# CRBN_60.net
KiCad netlist of a schematic drawn in EAGLE
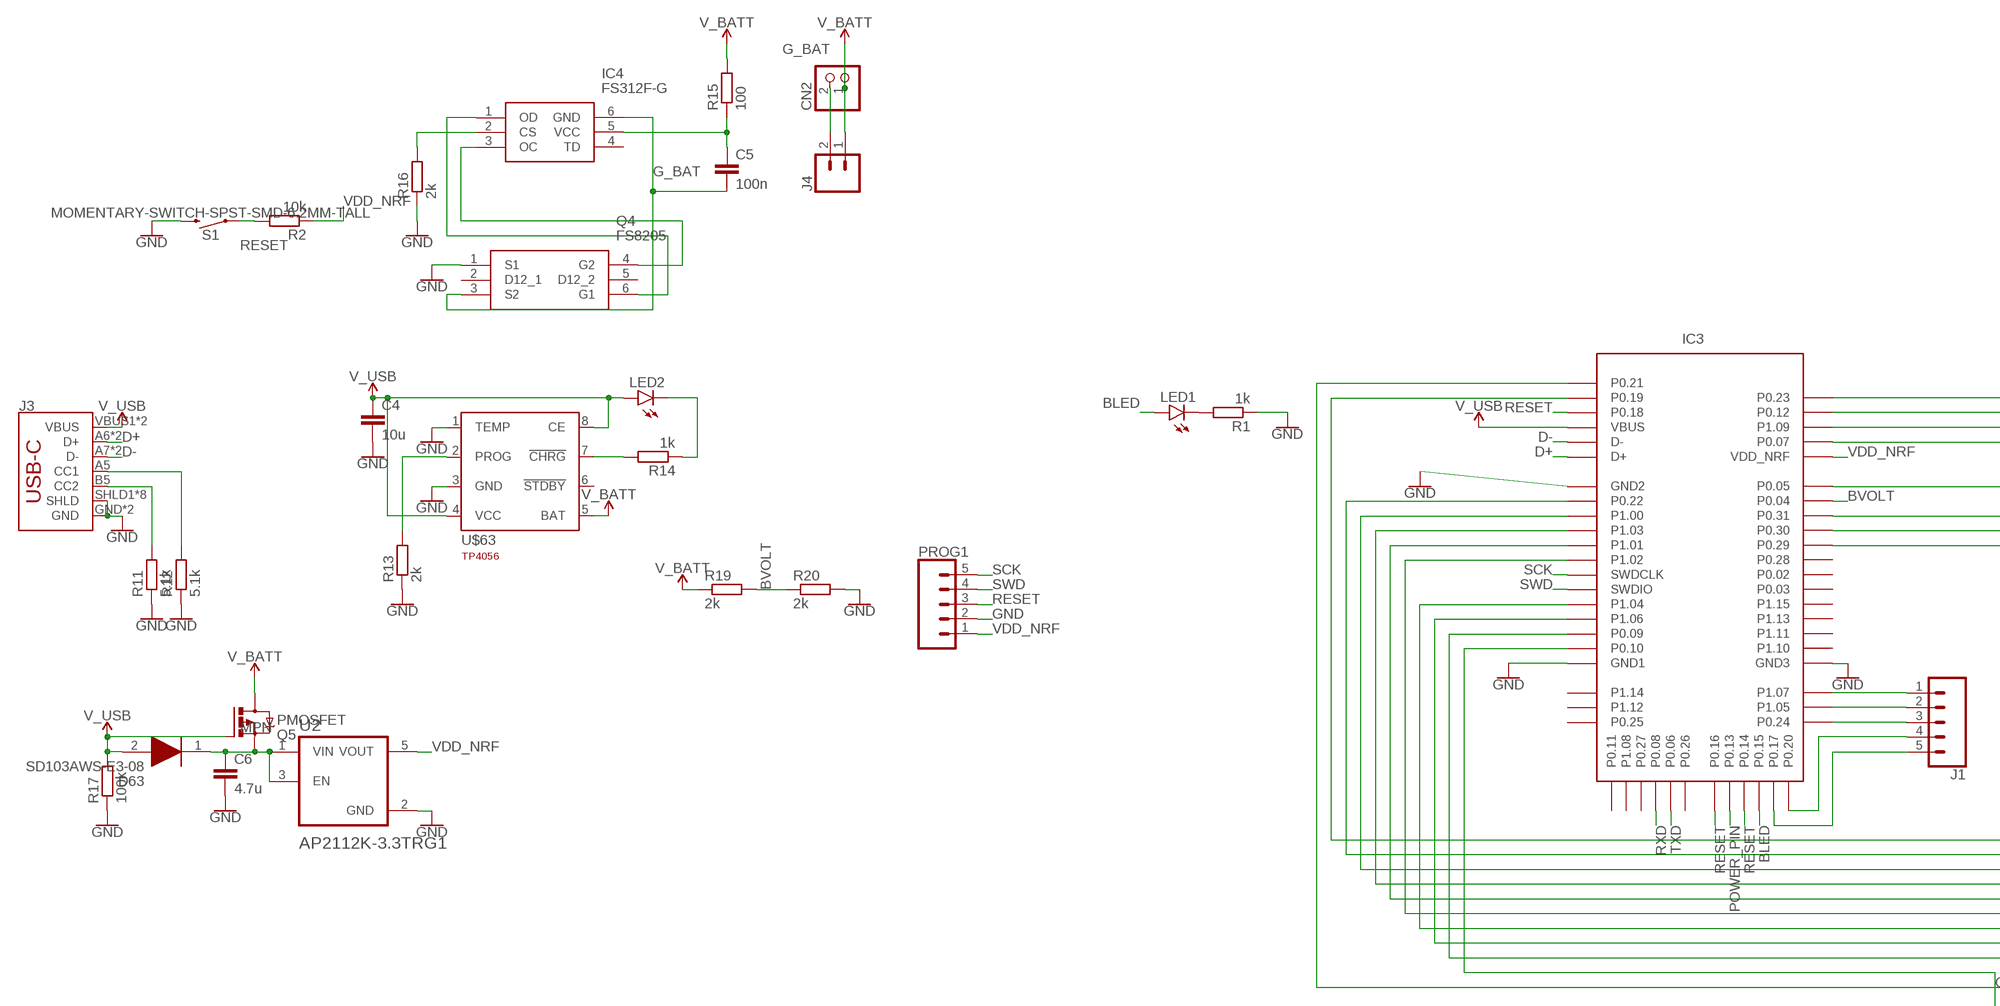
[diagram p0: schematic, sheet 1, part 1 of 2]
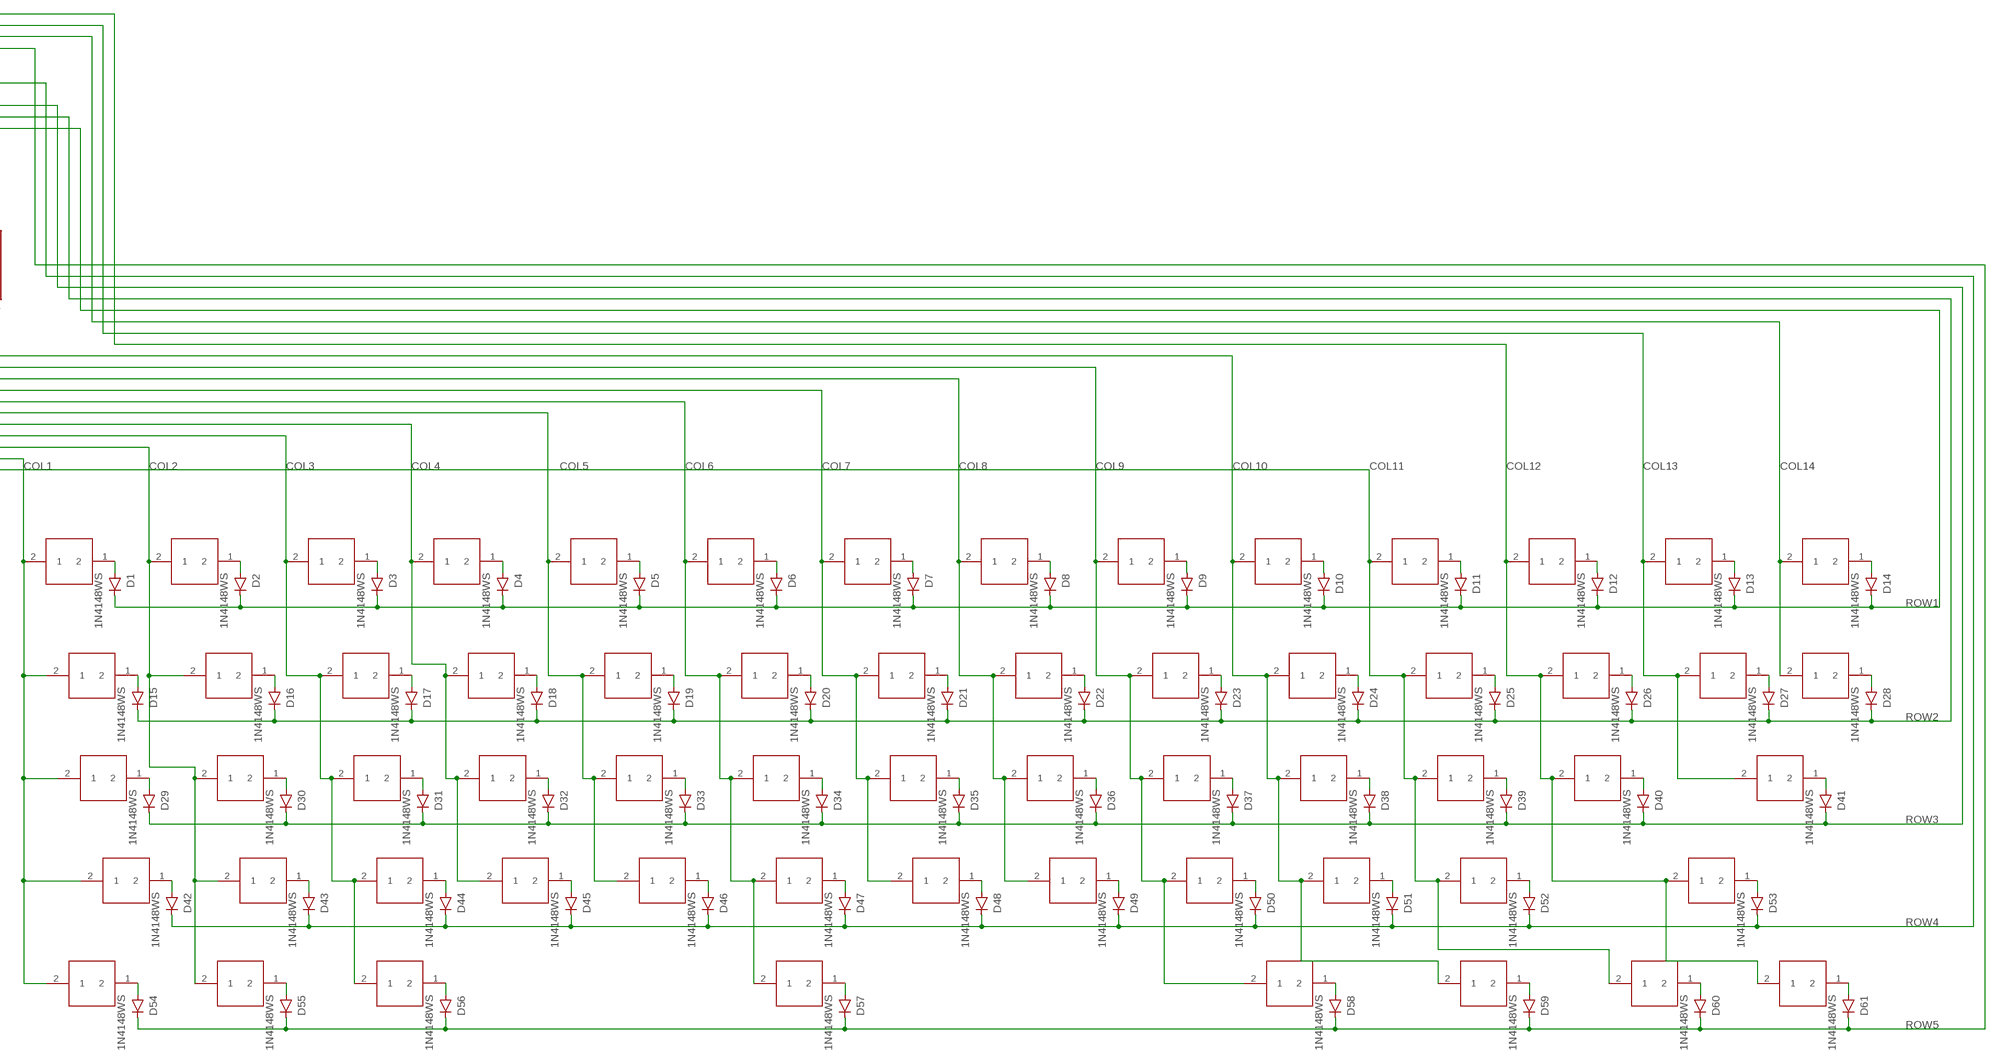
[diagram p1: schematic, sheet 1, part 2 of 2]

(export (version "E")
  (design (tool "Eeschema 10.0.6"))
  (components
    (comp (ref "C4")
      (value "10u")
      (footprint "eagle-import:C0603")
      (libsource (lib "eagle-import") (part "C-EUC0603"))
    )
    (comp (ref "C5")
      (value "100n")
      (footprint "eagle-import:C0603")
      (libsource (lib "eagle-import") (part "C-EUC0603"))
    )
    (comp (ref "C6")
      (value "4.7u")
      (footprint "eagle-import:C0603")
      (libsource (lib "eagle-import") (part "C-EUC0603"))
    )
    (comp (ref "CN2")
      (value "JST_2PIN-SMT")
      (footprint "eagle-import:JST-PH-2-SMT")
      (libsource (lib "eagle-import") (part "JST_2PIN-SMT"))
    )
    (comp (ref "D1")
      (value "1N4148WS")
      (footprint "eagle-import:SOD-323")
      (fields
        (field (name "DIGIKEY_PART_NUMBER") "1N4148WSFSTR-ND")
        (field (name "MANUFACTURER") "Diodes Incorporated")
        (field (name "CREATED_BY") "PCBLayout.com")
      )
      (libsource (lib "eagle-import") (part "1N4148WS"))
    )
    (comp (ref "D2")
      (value "1N4148WS")
      (footprint "eagle-import:SOD-323")
      (fields
        (field (name "DIGIKEY_PART_NUMBER") "1N4148WSFSTR-ND")
        (field (name "MANUFACTURER") "Diodes Incorporated")
        (field (name "CREATED_BY") "PCBLayout.com")
      )
      (libsource (lib "eagle-import") (part "1N4148WS"))
    )
    (comp (ref "D3")
      (value "1N4148WS")
      (footprint "eagle-import:SOD-323")
      (fields
        (field (name "DIGIKEY_PART_NUMBER") "1N4148WSFSTR-ND")
        (field (name "MANUFACTURER") "Diodes Incorporated")
        (field (name "CREATED_BY") "PCBLayout.com")
      )
      (libsource (lib "eagle-import") (part "1N4148WS"))
    )
    (comp (ref "D4")
      (value "1N4148WS")
      (footprint "eagle-import:SOD-323")
      (fields
        (field (name "DIGIKEY_PART_NUMBER") "1N4148WSFSTR-ND")
        (field (name "MANUFACTURER") "Diodes Incorporated")
        (field (name "CREATED_BY") "PCBLayout.com")
      )
      (libsource (lib "eagle-import") (part "1N4148WS"))
    )
    (comp (ref "D5")
      (value "1N4148WS")
      (footprint "eagle-import:SOD-323")
      (fields
        (field (name "DIGIKEY_PART_NUMBER") "1N4148WSFSTR-ND")
        (field (name "MANUFACTURER") "Diodes Incorporated")
        (field (name "CREATED_BY") "PCBLayout.com")
      )
      (libsource (lib "eagle-import") (part "1N4148WS"))
    )
    (comp (ref "D6")
      (value "1N4148WS")
      (footprint "eagle-import:SOD-323")
      (fields
        (field (name "DIGIKEY_PART_NUMBER") "1N4148WSFSTR-ND")
        (field (name "MANUFACTURER") "Diodes Incorporated")
        (field (name "CREATED_BY") "PCBLayout.com")
      )
      (libsource (lib "eagle-import") (part "1N4148WS"))
    )
    (comp (ref "D7")
      (value "1N4148WS")
      (footprint "eagle-import:SOD-323")
      (fields
        (field (name "DIGIKEY_PART_NUMBER") "1N4148WSFSTR-ND")
        (field (name "MANUFACTURER") "Diodes Incorporated")
        (field (name "CREATED_BY") "PCBLayout.com")
      )
      (libsource (lib "eagle-import") (part "1N4148WS"))
    )
    (comp (ref "D8")
      (value "1N4148WS")
      (footprint "eagle-import:SOD-323")
      (fields
        (field (name "DIGIKEY_PART_NUMBER") "1N4148WSFSTR-ND")
        (field (name "MANUFACTURER") "Diodes Incorporated")
        (field (name "CREATED_BY") "PCBLayout.com")
      )
      (libsource (lib "eagle-import") (part "1N4148WS"))
    )
    (comp (ref "D9")
      (value "1N4148WS")
      (footprint "eagle-import:SOD-323")
      (fields
        (field (name "DIGIKEY_PART_NUMBER") "1N4148WSFSTR-ND")
        (field (name "MANUFACTURER") "Diodes Incorporated")
        (field (name "CREATED_BY") "PCBLayout.com")
      )
      (libsource (lib "eagle-import") (part "1N4148WS"))
    )
    (comp (ref "D10")
      (value "1N4148WS")
      (footprint "eagle-import:SOD-323")
      (fields
        (field (name "DIGIKEY_PART_NUMBER") "1N4148WSFSTR-ND")
        (field (name "MANUFACTURER") "Diodes Incorporated")
        (field (name "CREATED_BY") "PCBLayout.com")
      )
      (libsource (lib "eagle-import") (part "1N4148WS"))
    )
    (comp (ref "D11")
      (value "1N4148WS")
      (footprint "eagle-import:SOD-323")
      (fields
        (field (name "DIGIKEY_PART_NUMBER") "1N4148WSFSTR-ND")
        (field (name "MANUFACTURER") "Diodes Incorporated")
        (field (name "CREATED_BY") "PCBLayout.com")
      )
      (libsource (lib "eagle-import") (part "1N4148WS"))
    )
    (comp (ref "D12")
      (value "1N4148WS")
      (footprint "eagle-import:SOD-323")
      (fields
        (field (name "DIGIKEY_PART_NUMBER") "1N4148WSFSTR-ND")
        (field (name "MANUFACTURER") "Diodes Incorporated")
        (field (name "CREATED_BY") "PCBLayout.com")
      )
      (libsource (lib "eagle-import") (part "1N4148WS"))
    )
    (comp (ref "D13")
      (value "1N4148WS")
      (footprint "eagle-import:SOD-323")
      (fields
        (field (name "DIGIKEY_PART_NUMBER") "1N4148WSFSTR-ND")
        (field (name "MANUFACTURER") "Diodes Incorporated")
        (field (name "CREATED_BY") "PCBLayout.com")
      )
      (libsource (lib "eagle-import") (part "1N4148WS"))
    )
    (comp (ref "D14")
      (value "1N4148WS")
      (footprint "eagle-import:SOD-323")
      (fields
        (field (name "DIGIKEY_PART_NUMBER") "1N4148WSFSTR-ND")
        (field (name "MANUFACTURER") "Diodes Incorporated")
        (field (name "CREATED_BY") "PCBLayout.com")
      )
      (libsource (lib "eagle-import") (part "1N4148WS"))
    )
    (comp (ref "D15")
      (value "1N4148WS")
      (footprint "eagle-import:SOD-323")
      (fields
        (field (name "DIGIKEY_PART_NUMBER") "1N4148WSFSTR-ND")
        (field (name "MANUFACTURER") "Diodes Incorporated")
        (field (name "CREATED_BY") "PCBLayout.com")
      )
      (libsource (lib "eagle-import") (part "1N4148WS"))
    )
    (comp (ref "D16")
      (value "1N4148WS")
      (footprint "eagle-import:SOD-323")
      (fields
        (field (name "DIGIKEY_PART_NUMBER") "1N4148WSFSTR-ND")
        (field (name "MANUFACTURER") "Diodes Incorporated")
        (field (name "CREATED_BY") "PCBLayout.com")
      )
      (libsource (lib "eagle-import") (part "1N4148WS"))
    )
    (comp (ref "D17")
      (value "1N4148WS")
      (footprint "eagle-import:SOD-323")
      (fields
        (field (name "DIGIKEY_PART_NUMBER") "1N4148WSFSTR-ND")
        (field (name "MANUFACTURER") "Diodes Incorporated")
        (field (name "CREATED_BY") "PCBLayout.com")
      )
      (libsource (lib "eagle-import") (part "1N4148WS"))
    )
    (comp (ref "D18")
      (value "1N4148WS")
      (footprint "eagle-import:SOD-323")
      (fields
        (field (name "DIGIKEY_PART_NUMBER") "1N4148WSFSTR-ND")
        (field (name "MANUFACTURER") "Diodes Incorporated")
        (field (name "CREATED_BY") "PCBLayout.com")
      )
      (libsource (lib "eagle-import") (part "1N4148WS"))
    )
    (comp (ref "D19")
      (value "1N4148WS")
      (footprint "eagle-import:SOD-323")
      (fields
        (field (name "DIGIKEY_PART_NUMBER") "1N4148WSFSTR-ND")
        (field (name "MANUFACTURER") "Diodes Incorporated")
        (field (name "CREATED_BY") "PCBLayout.com")
      )
      (libsource (lib "eagle-import") (part "1N4148WS"))
    )
    (comp (ref "D20")
      (value "1N4148WS")
      (footprint "eagle-import:SOD-323")
      (fields
        (field (name "DIGIKEY_PART_NUMBER") "1N4148WSFSTR-ND")
        (field (name "MANUFACTURER") "Diodes Incorporated")
        (field (name "CREATED_BY") "PCBLayout.com")
      )
      (libsource (lib "eagle-import") (part "1N4148WS"))
    )
    (comp (ref "D21")
      (value "1N4148WS")
      (footprint "eagle-import:SOD-323")
      (fields
        (field (name "DIGIKEY_PART_NUMBER") "1N4148WSFSTR-ND")
        (field (name "MANUFACTURER") "Diodes Incorporated")
        (field (name "CREATED_BY") "PCBLayout.com")
      )
      (libsource (lib "eagle-import") (part "1N4148WS"))
    )
    (comp (ref "D22")
      (value "1N4148WS")
      (footprint "eagle-import:SOD-323")
      (fields
        (field (name "DIGIKEY_PART_NUMBER") "1N4148WSFSTR-ND")
        (field (name "MANUFACTURER") "Diodes Incorporated")
        (field (name "CREATED_BY") "PCBLayout.com")
      )
      (libsource (lib "eagle-import") (part "1N4148WS"))
    )
    (comp (ref "D23")
      (value "1N4148WS")
      (footprint "eagle-import:SOD-323")
      (fields
        (field (name "DIGIKEY_PART_NUMBER") "1N4148WSFSTR-ND")
        (field (name "MANUFACTURER") "Diodes Incorporated")
        (field (name "CREATED_BY") "PCBLayout.com")
      )
      (libsource (lib "eagle-import") (part "1N4148WS"))
    )
    (comp (ref "D24")
      (value "1N4148WS")
      (footprint "eagle-import:SOD-323")
      (fields
        (field (name "DIGIKEY_PART_NUMBER") "1N4148WSFSTR-ND")
        (field (name "MANUFACTURER") "Diodes Incorporated")
        (field (name "CREATED_BY") "PCBLayout.com")
      )
      (libsource (lib "eagle-import") (part "1N4148WS"))
    )
    (comp (ref "D25")
      (value "1N4148WS")
      (footprint "eagle-import:SOD-323")
      (fields
        (field (name "DIGIKEY_PART_NUMBER") "1N4148WSFSTR-ND")
        (field (name "MANUFACTURER") "Diodes Incorporated")
        (field (name "CREATED_BY") "PCBLayout.com")
      )
      (libsource (lib "eagle-import") (part "1N4148WS"))
    )
    (comp (ref "D26")
      (value "1N4148WS")
      (footprint "eagle-import:SOD-323")
      (fields
        (field (name "DIGIKEY_PART_NUMBER") "1N4148WSFSTR-ND")
        (field (name "MANUFACTURER") "Diodes Incorporated")
        (field (name "CREATED_BY") "PCBLayout.com")
      )
      (libsource (lib "eagle-import") (part "1N4148WS"))
    )
    (comp (ref "D27")
      (value "1N4148WS")
      (footprint "eagle-import:SOD-323")
      (fields
        (field (name "DIGIKEY_PART_NUMBER") "1N4148WSFSTR-ND")
        (field (name "MANUFACTURER") "Diodes Incorporated")
        (field (name "CREATED_BY") "PCBLayout.com")
      )
      (libsource (lib "eagle-import") (part "1N4148WS"))
    )
    (comp (ref "D28")
      (value "1N4148WS")
      (footprint "eagle-import:SOD-323")
      (fields
        (field (name "DIGIKEY_PART_NUMBER") "1N4148WSFSTR-ND")
        (field (name "MANUFACTURER") "Diodes Incorporated")
        (field (name "CREATED_BY") "PCBLayout.com")
      )
      (libsource (lib "eagle-import") (part "1N4148WS"))
    )
    (comp (ref "D29")
      (value "1N4148WS")
      (footprint "eagle-import:SOD-323")
      (fields
        (field (name "DIGIKEY_PART_NUMBER") "1N4148WSFSTR-ND")
        (field (name "MANUFACTURER") "Diodes Incorporated")
        (field (name "CREATED_BY") "PCBLayout.com")
      )
      (libsource (lib "eagle-import") (part "1N4148WS"))
    )
    (comp (ref "D30")
      (value "1N4148WS")
      (footprint "eagle-import:SOD-323")
      (fields
        (field (name "DIGIKEY_PART_NUMBER") "1N4148WSFSTR-ND")
        (field (name "MANUFACTURER") "Diodes Incorporated")
        (field (name "CREATED_BY") "PCBLayout.com")
      )
      (libsource (lib "eagle-import") (part "1N4148WS"))
    )
    (comp (ref "D31")
      (value "1N4148WS")
      (footprint "eagle-import:SOD-323")
      (fields
        (field (name "DIGIKEY_PART_NUMBER") "1N4148WSFSTR-ND")
        (field (name "MANUFACTURER") "Diodes Incorporated")
        (field (name "CREATED_BY") "PCBLayout.com")
      )
      (libsource (lib "eagle-import") (part "1N4148WS"))
    )
    (comp (ref "D32")
      (value "1N4148WS")
      (footprint "eagle-import:SOD-323")
      (fields
        (field (name "DIGIKEY_PART_NUMBER") "1N4148WSFSTR-ND")
        (field (name "MANUFACTURER") "Diodes Incorporated")
        (field (name "CREATED_BY") "PCBLayout.com")
      )
      (libsource (lib "eagle-import") (part "1N4148WS"))
    )
    (comp (ref "D33")
      (value "1N4148WS")
      (footprint "eagle-import:SOD-323")
      (fields
        (field (name "DIGIKEY_PART_NUMBER") "1N4148WSFSTR-ND")
        (field (name "MANUFACTURER") "Diodes Incorporated")
        (field (name "CREATED_BY") "PCBLayout.com")
      )
      (libsource (lib "eagle-import") (part "1N4148WS"))
    )
    (comp (ref "D34")
      (value "1N4148WS")
      (footprint "eagle-import:SOD-323")
      (fields
        (field (name "DIGIKEY_PART_NUMBER") "1N4148WSFSTR-ND")
        (field (name "MANUFACTURER") "Diodes Incorporated")
        (field (name "CREATED_BY") "PCBLayout.com")
      )
      (libsource (lib "eagle-import") (part "1N4148WS"))
    )
    (comp (ref "D35")
      (value "1N4148WS")
      (footprint "eagle-import:SOD-323")
      (fields
        (field (name "DIGIKEY_PART_NUMBER") "1N4148WSFSTR-ND")
        (field (name "MANUFACTURER") "Diodes Incorporated")
        (field (name "CREATED_BY") "PCBLayout.com")
      )
      (libsource (lib "eagle-import") (part "1N4148WS"))
    )
    (comp (ref "D36")
      (value "1N4148WS")
      (footprint "eagle-import:SOD-323")
      (fields
        (field (name "DIGIKEY_PART_NUMBER") "1N4148WSFSTR-ND")
        (field (name "MANUFACTURER") "Diodes Incorporated")
        (field (name "CREATED_BY") "PCBLayout.com")
      )
      (libsource (lib "eagle-import") (part "1N4148WS"))
    )
    (comp (ref "D37")
      (value "1N4148WS")
      (footprint "eagle-import:SOD-323")
      (fields
        (field (name "DIGIKEY_PART_NUMBER") "1N4148WSFSTR-ND")
        (field (name "MANUFACTURER") "Diodes Incorporated")
        (field (name "CREATED_BY") "PCBLayout.com")
      )
      (libsource (lib "eagle-import") (part "1N4148WS"))
    )
    (comp (ref "D38")
      (value "1N4148WS")
      (footprint "eagle-import:SOD-323")
      (fields
        (field (name "DIGIKEY_PART_NUMBER") "1N4148WSFSTR-ND")
        (field (name "MANUFACTURER") "Diodes Incorporated")
        (field (name "CREATED_BY") "PCBLayout.com")
      )
      (libsource (lib "eagle-import") (part "1N4148WS"))
    )
    (comp (ref "D39")
      (value "1N4148WS")
      (footprint "eagle-import:SOD-323")
      (fields
        (field (name "DIGIKEY_PART_NUMBER") "1N4148WSFSTR-ND")
        (field (name "MANUFACTURER") "Diodes Incorporated")
        (field (name "CREATED_BY") "PCBLayout.com")
      )
      (libsource (lib "eagle-import") (part "1N4148WS"))
    )
    (comp (ref "D40")
      (value "1N4148WS")
      (footprint "eagle-import:SOD-323")
      (fields
        (field (name "DIGIKEY_PART_NUMBER") "1N4148WSFSTR-ND")
        (field (name "MANUFACTURER") "Diodes Incorporated")
        (field (name "CREATED_BY") "PCBLayout.com")
      )
      (libsource (lib "eagle-import") (part "1N4148WS"))
    )
    (comp (ref "D41")
      (value "1N4148WS")
      (footprint "eagle-import:SOD-323")
      (fields
        (field (name "DIGIKEY_PART_NUMBER") "1N4148WSFSTR-ND")
        (field (name "MANUFACTURER") "Diodes Incorporated")
        (field (name "CREATED_BY") "PCBLayout.com")
      )
      (libsource (lib "eagle-import") (part "1N4148WS"))
    )
    (comp (ref "D42")
      (value "1N4148WS")
      (footprint "eagle-import:SOD-323")
      (fields
        (field (name "DIGIKEY_PART_NUMBER") "1N4148WSFSTR-ND")
        (field (name "MANUFACTURER") "Diodes Incorporated")
        (field (name "CREATED_BY") "PCBLayout.com")
      )
      (libsource (lib "eagle-import") (part "1N4148WS"))
    )
    (comp (ref "D43")
      (value "1N4148WS")
      (footprint "eagle-import:SOD-323")
      (fields
        (field (name "DIGIKEY_PART_NUMBER") "1N4148WSFSTR-ND")
        (field (name "MANUFACTURER") "Diodes Incorporated")
        (field (name "CREATED_BY") "PCBLayout.com")
      )
      (libsource (lib "eagle-import") (part "1N4148WS"))
    )
    (comp (ref "D44")
      (value "1N4148WS")
      (footprint "eagle-import:SOD-323")
      (fields
        (field (name "DIGIKEY_PART_NUMBER") "1N4148WSFSTR-ND")
        (field (name "MANUFACTURER") "Diodes Incorporated")
        (field (name "CREATED_BY") "PCBLayout.com")
      )
      (libsource (lib "eagle-import") (part "1N4148WS"))
    )
    (comp (ref "D45")
      (value "1N4148WS")
      (footprint "eagle-import:SOD-323")
      (fields
        (field (name "DIGIKEY_PART_NUMBER") "1N4148WSFSTR-ND")
        (field (name "MANUFACTURER") "Diodes Incorporated")
        (field (name "CREATED_BY") "PCBLayout.com")
      )
      (libsource (lib "eagle-import") (part "1N4148WS"))
    )
    (comp (ref "D46")
      (value "1N4148WS")
      (footprint "eagle-import:SOD-323")
      (fields
        (field (name "DIGIKEY_PART_NUMBER") "1N4148WSFSTR-ND")
        (field (name "MANUFACTURER") "Diodes Incorporated")
        (field (name "CREATED_BY") "PCBLayout.com")
      )
      (libsource (lib "eagle-import") (part "1N4148WS"))
    )
    (comp (ref "D47")
      (value "1N4148WS")
      (footprint "eagle-import:SOD-323")
      (fields
        (field (name "DIGIKEY_PART_NUMBER") "1N4148WSFSTR-ND")
        (field (name "MANUFACTURER") "Diodes Incorporated")
        (field (name "CREATED_BY") "PCBLayout.com")
      )
      (libsource (lib "eagle-import") (part "1N4148WS"))
    )
    (comp (ref "D48")
      (value "1N4148WS")
      (footprint "eagle-import:SOD-323")
      (fields
        (field (name "DIGIKEY_PART_NUMBER") "1N4148WSFSTR-ND")
        (field (name "MANUFACTURER") "Diodes Incorporated")
        (field (name "CREATED_BY") "PCBLayout.com")
      )
      (libsource (lib "eagle-import") (part "1N4148WS"))
    )
    (comp (ref "D49")
      (value "1N4148WS")
      (footprint "eagle-import:SOD-323")
      (fields
        (field (name "DIGIKEY_PART_NUMBER") "1N4148WSFSTR-ND")
        (field (name "MANUFACTURER") "Diodes Incorporated")
        (field (name "CREATED_BY") "PCBLayout.com")
      )
      (libsource (lib "eagle-import") (part "1N4148WS"))
    )
    (comp (ref "D50")
      (value "1N4148WS")
      (footprint "eagle-import:SOD-323")
      (fields
        (field (name "DIGIKEY_PART_NUMBER") "1N4148WSFSTR-ND")
        (field (name "MANUFACTURER") "Diodes Incorporated")
        (field (name "CREATED_BY") "PCBLayout.com")
      )
      (libsource (lib "eagle-import") (part "1N4148WS"))
    )
    (comp (ref "D51")
      (value "1N4148WS")
      (footprint "eagle-import:SOD-323")
      (fields
        (field (name "DIGIKEY_PART_NUMBER") "1N4148WSFSTR-ND")
        (field (name "MANUFACTURER") "Diodes Incorporated")
        (field (name "CREATED_BY") "PCBLayout.com")
      )
      (libsource (lib "eagle-import") (part "1N4148WS"))
    )
    (comp (ref "D52")
      (value "1N4148WS")
      (footprint "eagle-import:SOD-323")
      (fields
        (field (name "DIGIKEY_PART_NUMBER") "1N4148WSFSTR-ND")
        (field (name "MANUFACTURER") "Diodes Incorporated")
        (field (name "CREATED_BY") "PCBLayout.com")
      )
      (libsource (lib "eagle-import") (part "1N4148WS"))
    )
    (comp (ref "D53")
      (value "1N4148WS")
      (footprint "eagle-import:SOD-323")
      (fields
        (field (name "DIGIKEY_PART_NUMBER") "1N4148WSFSTR-ND")
        (field (name "MANUFACTURER") "Diodes Incorporated")
        (field (name "CREATED_BY") "PCBLayout.com")
      )
      (libsource (lib "eagle-import") (part "1N4148WS"))
    )
    (comp (ref "D54")
      (value "1N4148WS")
      (footprint "eagle-import:SOD-323")
      (fields
        (field (name "DIGIKEY_PART_NUMBER") "1N4148WSFSTR-ND")
        (field (name "MANUFACTURER") "Diodes Incorporated")
        (field (name "CREATED_BY") "PCBLayout.com")
      )
      (libsource (lib "eagle-import") (part "1N4148WS"))
    )
    (comp (ref "D55")
      (value "1N4148WS")
      (footprint "eagle-import:SOD-323")
      (fields
        (field (name "DIGIKEY_PART_NUMBER") "1N4148WSFSTR-ND")
        (field (name "MANUFACTURER") "Diodes Incorporated")
        (field (name "CREATED_BY") "PCBLayout.com")
      )
      (libsource (lib "eagle-import") (part "1N4148WS"))
    )
    (comp (ref "D56")
      (value "1N4148WS")
      (footprint "eagle-import:SOD-323")
      (fields
        (field (name "DIGIKEY_PART_NUMBER") "1N4148WSFSTR-ND")
        (field (name "MANUFACTURER") "Diodes Incorporated")
        (field (name "CREATED_BY") "PCBLayout.com")
      )
      (libsource (lib "eagle-import") (part "1N4148WS"))
    )
    (comp (ref "D57")
      (value "1N4148WS")
      (footprint "eagle-import:SOD-323")
      (fields
        (field (name "DIGIKEY_PART_NUMBER") "1N4148WSFSTR-ND")
        (field (name "MANUFACTURER") "Diodes Incorporated")
        (field (name "CREATED_BY") "PCBLayout.com")
      )
      (libsource (lib "eagle-import") (part "1N4148WS"))
    )
    (comp (ref "D58")
      (value "1N4148WS")
      (footprint "eagle-import:SOD-323")
      (fields
        (field (name "DIGIKEY_PART_NUMBER") "1N4148WSFSTR-ND")
        (field (name "MANUFACTURER") "Diodes Incorporated")
        (field (name "CREATED_BY") "PCBLayout.com")
      )
      (libsource (lib "eagle-import") (part "1N4148WS"))
    )
    (comp (ref "D59")
      (value "1N4148WS")
      (footprint "eagle-import:SOD-323")
      (fields
        (field (name "DIGIKEY_PART_NUMBER") "1N4148WSFSTR-ND")
        (field (name "MANUFACTURER") "Diodes Incorporated")
        (field (name "CREATED_BY") "PCBLayout.com")
      )
      (libsource (lib "eagle-import") (part "1N4148WS"))
    )
    (comp (ref "D60")
      (value "1N4148WS")
      (footprint "eagle-import:SOD-323")
      (fields
        (field (name "DIGIKEY_PART_NUMBER") "1N4148WSFSTR-ND")
        (field (name "MANUFACTURER") "Diodes Incorporated")
        (field (name "CREATED_BY") "PCBLayout.com")
      )
      (libsource (lib "eagle-import") (part "1N4148WS"))
    )
    (comp (ref "D61")
      (value "1N4148WS")
      (footprint "eagle-import:SOD-323")
      (fields
        (field (name "DIGIKEY_PART_NUMBER") "1N4148WSFSTR-ND")
        (field (name "MANUFACTURER") "Diodes Incorporated")
        (field (name "CREATED_BY") "PCBLayout.com")
      )
      (libsource (lib "eagle-import") (part "1N4148WS"))
    )
    (comp (ref "D63")
      (value "SD103AWS-E3-08")
      (footprint "eagle-import:SOD2713X115N")
      (fields (field (name "MOUSER_PART_NUMBER") "78-SD103AWS-E3-08"))
      (libsource (lib "eagle-import") (part "SD103AWS-E3-08"))
    )
    (comp (ref "IC3")
      (value "HOLYIOT_18010")
      (footprint "eagle-import:PCBCOMPONENT_1")
      (libsource (lib "eagle-import") (part "HOLYIOT_18010"))
    )
    (comp (ref "IC4")
      (value "FS312F-G")
      (footprint "eagle-import:SOT95P280X145-6N")
      (libsource (lib "eagle-import") (part "FS312F-G"))
    )
    (comp (ref "J1")
      (value "CONN_051.27MM")
      (footprint "eagle-import:1X05_1.27MM")
      (libsource (lib "eagle-import") (part "CONN_051.27MM"))
    )
    (comp (ref "J3")
      (value "SPARKFUN-CONNECTORS_USB_C16PIN")
      (footprint "eagle-import:SPARKFUN-CONNECTORS_USB-C-16P")
      (libsource (lib "eagle-import") (part "SPARKFUN-CONNECTORS_USB_C16PIN"))
    )
    (comp (ref "J4")
      (value "CONN_02")
      (footprint "eagle-import:1X02")
      (libsource (lib "eagle-import") (part "CONN_02"))
    )
    (comp (ref "LED1")
      (value "LEDSML0603")
      (footprint "eagle-import:SML0603")
      (libsource (lib "eagle-import") (part "LEDSML0603"))
    )
    (comp (ref "LED2")
      (value "LEDSML0603")
      (footprint "eagle-import:SML0603")
      (libsource (lib "eagle-import") (part "LEDSML0603"))
    )
    (comp (ref "PROG1")
      (value "CONN_05")
      (footprint "eagle-import:1X05")
      (libsource (lib "eagle-import") (part "CONN_05"))
    )
    (comp (ref "Q4")
      (value "FS8205")
      (footprint "eagle-import:FS8205")
      (libsource (lib "eagle-import") (part "FS8205"))
    )
    (comp (ref "Q5")
      (value "PMOSFET")
      (footprint "eagle-import:SOT23")
      (fields (field (name "MPN") "SL2301S"))
      (libsource (lib "eagle-import") (part "PMOSFETSOT23_"))
    )
    (comp (ref "R1")
      (value "1k")
      (footprint "eagle-import:R0603")
      (libsource (lib "eagle-import") (part "R-EU_R0603"))
    )
    (comp (ref "R2")
      (value "10k")
      (footprint "eagle-import:R0603")
      (libsource (lib "eagle-import") (part "R-EU_R0603"))
    )
    (comp (ref "R11")
      (value "5.1k")
      (footprint "eagle-import:R0603")
      (libsource (lib "eagle-import") (part "R-EU_R0603"))
    )
    (comp (ref "R12")
      (value "5.1k")
      (footprint "eagle-import:R0603")
      (libsource (lib "eagle-import") (part "R-EU_R0603"))
    )
    (comp (ref "R13")
      (value "2k")
      (footprint "eagle-import:R0603")
      (libsource (lib "eagle-import") (part "R-EU_R0603"))
    )
    (comp (ref "R14")
      (value "1k")
      (footprint "eagle-import:R0603")
      (libsource (lib "eagle-import") (part "R-EU_R0603"))
    )
    (comp (ref "R15")
      (value "100")
      (footprint "eagle-import:R0603")
      (libsource (lib "eagle-import") (part "R-EU_R0603"))
    )
    (comp (ref "R16")
      (value "2k")
      (footprint "eagle-import:R0603")
      (libsource (lib "eagle-import") (part "R-EU_R0603"))
    )
    (comp (ref "R17")
      (value "100k")
      (footprint "eagle-import:R0603")
      (libsource (lib "eagle-import") (part "R-EU_R0603"))
    )
    (comp (ref "R19")
      (value "2k")
      (footprint "eagle-import:R0603")
      (libsource (lib "eagle-import") (part "R-EU_R0603"))
    )
    (comp (ref "R20")
      (value "2k")
      (footprint "eagle-import:R0603")
      (libsource (lib "eagle-import") (part "R-EU_R0603"))
    )
    (comp (ref "S1")
      (value "MOMENTARY-SWITCH-SPST-SMD-6.2MM-TALL")
      (footprint "eagle-import:TACTILE_SWITCH_SMD_6.2MM_TALL")
      (libsource (lib "eagle-import") (part "MOMENTARY-SWITCH-SPST-SMD-6.2MM-TALL"))
    )
    (comp (ref "U$1")
      (value "CHERRY")
      (footprint "eagle-import:CHERRY")
      (libsource (lib "eagle-import") (part "CHERRY"))
    )
    (comp (ref "U$2")
      (value "CHERRY")
      (footprint "eagle-import:CHERRY")
      (libsource (lib "eagle-import") (part "CHERRY"))
    )
    (comp (ref "U$3")
      (value "CHERRY")
      (footprint "eagle-import:CHERRY")
      (libsource (lib "eagle-import") (part "CHERRY"))
    )
    (comp (ref "U$4")
      (value "CHERRY")
      (footprint "eagle-import:CHERRY")
      (libsource (lib "eagle-import") (part "CHERRY"))
    )
    (comp (ref "U$5")
      (value "CHERRY")
      (footprint "eagle-import:CHERRY")
      (libsource (lib "eagle-import") (part "CHERRY"))
    )
    (comp (ref "U$6")
      (value "CHERRY")
      (footprint "eagle-import:CHERRY")
      (libsource (lib "eagle-import") (part "CHERRY"))
    )
    (comp (ref "U$7")
      (value "CHERRY")
      (footprint "eagle-import:CHERRY")
      (libsource (lib "eagle-import") (part "CHERRY"))
    )
    (comp (ref "U$8")
      (value "CHERRY")
      (footprint "eagle-import:CHERRY")
      (libsource (lib "eagle-import") (part "CHERRY"))
    )
    (comp (ref "U$9")
      (value "CHERRY")
      (footprint "eagle-import:CHERRY")
      (libsource (lib "eagle-import") (part "CHERRY"))
    )
    (comp (ref "U$10")
      (value "CHERRY")
      (footprint "eagle-import:CHERRY")
      (libsource (lib "eagle-import") (part "CHERRY"))
    )
    (comp (ref "U$11")
      (value "CHERRY")
      (footprint "eagle-import:CHERRY")
      (libsource (lib "eagle-import") (part "CHERRY"))
    )
    (comp (ref "U$12")
      (value "CHERRY")
      (footprint "eagle-import:CHERRY")
      (libsource (lib "eagle-import") (part "CHERRY"))
    )
    (comp (ref "U$13")
      (value "CHERRY")
      (footprint "eagle-import:CHERRY")
      (libsource (lib "eagle-import") (part "CHERRY"))
    )
    (comp (ref "U$14")
      (value "CHERRY")
      (footprint "eagle-import:CHERRY")
      (libsource (lib "eagle-import") (part "CHERRY"))
    )
    (comp (ref "U$15")
      (value "CHERRY")
      (footprint "eagle-import:CHERRY")
      (libsource (lib "eagle-import") (part "CHERRY"))
    )
    (comp (ref "U$16")
      (value "CHERRY")
      (footprint "eagle-import:CHERRY")
      (libsource (lib "eagle-import") (part "CHERRY"))
    )
    (comp (ref "U$17")
      (value "CHERRY")
      (footprint "eagle-import:CHERRY")
      (libsource (lib "eagle-import") (part "CHERRY"))
    )
    (comp (ref "U$18")
      (value "CHERRY")
      (footprint "eagle-import:CHERRY")
      (libsource (lib "eagle-import") (part "CHERRY"))
    )
    (comp (ref "U$19")
      (value "CHERRY")
      (footprint "eagle-import:CHERRY")
      (libsource (lib "eagle-import") (part "CHERRY"))
    )
    (comp (ref "U$20")
      (value "CHERRY")
      (footprint "eagle-import:CHERRY")
      (libsource (lib "eagle-import") (part "CHERRY"))
    )
    (comp (ref "U$21")
      (value "CHERRY")
      (footprint "eagle-import:CHERRY")
      (libsource (lib "eagle-import") (part "CHERRY"))
    )
    (comp (ref "U$22")
      (value "CHERRY")
      (footprint "eagle-import:CHERRY")
      (libsource (lib "eagle-import") (part "CHERRY"))
    )
    (comp (ref "U$23")
      (value "CHERRY")
      (footprint "eagle-import:CHERRY")
      (libsource (lib "eagle-import") (part "CHERRY"))
    )
    (comp (ref "U$24")
      (value "CHERRY")
      (footprint "eagle-import:CHERRY")
      (libsource (lib "eagle-import") (part "CHERRY"))
    )
    (comp (ref "U$25")
      (value "CHERRY")
      (footprint "eagle-import:CHERRY")
      (libsource (lib "eagle-import") (part "CHERRY"))
    )
    (comp (ref "U$26")
      (value "CHERRY")
      (footprint "eagle-import:CHERRY")
      (libsource (lib "eagle-import") (part "CHERRY"))
    )
    (comp (ref "U$27")
      (value "CHERRY")
      (footprint "eagle-import:CHERRY")
      (libsource (lib "eagle-import") (part "CHERRY"))
    )
    (comp (ref "U$28")
      (value "CHERRY")
      (footprint "eagle-import:CHERRY")
      (libsource (lib "eagle-import") (part "CHERRY"))
    )
    (comp (ref "U$29")
      (value "CHERRY")
      (footprint "eagle-import:CHERRY")
      (libsource (lib "eagle-import") (part "CHERRY"))
    )
    (comp (ref "U$30")
      (value "CHERRY")
      (footprint "eagle-import:CHERRY")
      (libsource (lib "eagle-import") (part "CHERRY"))
    )
    (comp (ref "U$31")
      (value "CHERRY")
      (footprint "eagle-import:CHERRY")
      (libsource (lib "eagle-import") (part "CHERRY"))
    )
    (comp (ref "U$32")
      (value "CHERRY")
      (footprint "eagle-import:CHERRY")
      (libsource (lib "eagle-import") (part "CHERRY"))
    )
    (comp (ref "U$33")
      (value "CHERRY")
      (footprint "eagle-import:CHERRY")
      (libsource (lib "eagle-import") (part "CHERRY"))
    )
    (comp (ref "U$34")
      (value "CHERRY")
      (footprint "eagle-import:CHERRY")
      (libsource (lib "eagle-import") (part "CHERRY"))
    )
    (comp (ref "U$35")
      (value "CHERRY")
      (footprint "eagle-import:CHERRY")
      (libsource (lib "eagle-import") (part "CHERRY"))
    )
    (comp (ref "U$36")
      (value "CHERRY")
      (footprint "eagle-import:CHERRY")
      (libsource (lib "eagle-import") (part "CHERRY"))
    )
    (comp (ref "U$37")
      (value "CHERRY")
      (footprint "eagle-import:CHERRY")
      (libsource (lib "eagle-import") (part "CHERRY"))
    )
    (comp (ref "U$38")
      (value "CHERRY")
      (footprint "eagle-import:CHERRY")
      (libsource (lib "eagle-import") (part "CHERRY"))
    )
    (comp (ref "U$39")
      (value "CHERRY")
      (footprint "eagle-import:CHERRY")
      (libsource (lib "eagle-import") (part "CHERRY"))
    )
    (comp (ref "U$40")
      (value "CHERRY")
      (footprint "eagle-import:CHERRY")
      (libsource (lib "eagle-import") (part "CHERRY"))
    )
    (comp (ref "U$41")
      (value "CHERRY")
      (footprint "eagle-import:CHERRY")
      (libsource (lib "eagle-import") (part "CHERRY"))
    )
    (comp (ref "U$42")
      (value "CHERRY")
      (footprint "eagle-import:CHERRY")
      (libsource (lib "eagle-import") (part "CHERRY"))
    )
    (comp (ref "U$43")
      (value "CHERRY")
      (footprint "eagle-import:CHERRY")
      (libsource (lib "eagle-import") (part "CHERRY"))
    )
    (comp (ref "U$44")
      (value "CHERRY")
      (footprint "eagle-import:CHERRY")
      (libsource (lib "eagle-import") (part "CHERRY"))
    )
    (comp (ref "U$45")
      (value "CHERRY")
      (footprint "eagle-import:CHERRY")
      (libsource (lib "eagle-import") (part "CHERRY"))
    )
    (comp (ref "U$46")
      (value "CHERRY")
      (footprint "eagle-import:CHERRY")
      (libsource (lib "eagle-import") (part "CHERRY"))
    )
    (comp (ref "U$47")
      (value "CHERRY")
      (footprint "eagle-import:CHERRY")
      (libsource (lib "eagle-import") (part "CHERRY"))
    )
    (comp (ref "U$48")
      (value "CHERRY")
      (footprint "eagle-import:CHERRY")
      (libsource (lib "eagle-import") (part "CHERRY"))
    )
    (comp (ref "U$49")
      (value "CHERRY")
      (footprint "eagle-import:CHERRY")
      (libsource (lib "eagle-import") (part "CHERRY"))
    )
    (comp (ref "U$50")
      (value "CHERRY")
      (footprint "eagle-import:CHERRY")
      (libsource (lib "eagle-import") (part "CHERRY"))
    )
    (comp (ref "U$51")
      (value "CHERRY")
      (footprint "eagle-import:CHERRY")
      (libsource (lib "eagle-import") (part "CHERRY"))
    )
    (comp (ref "U$52")
      (value "CHERRY")
      (footprint "eagle-import:CHERRY")
      (libsource (lib "eagle-import") (part "CHERRY"))
    )
    (comp (ref "U$53")
      (value "CHERRY")
      (footprint "eagle-import:CHERRY")
      (libsource (lib "eagle-import") (part "CHERRY"))
    )
    (comp (ref "U$54")
      (value "CHERRY")
      (footprint "eagle-import:CHERRY")
      (libsource (lib "eagle-import") (part "CHERRY"))
    )
    (comp (ref "U$55")
      (value "CHERRY")
      (footprint "eagle-import:CHERRY")
      (libsource (lib "eagle-import") (part "CHERRY"))
    )
    (comp (ref "U$56")
      (value "CHERRY")
      (footprint "eagle-import:CHERRY")
      (libsource (lib "eagle-import") (part "CHERRY"))
    )
    (comp (ref "U$57")
      (value "CHERRY")
      (footprint "eagle-import:CHERRY")
      (libsource (lib "eagle-import") (part "CHERRY"))
    )
    (comp (ref "U$58")
      (value "CHERRY")
      (footprint "eagle-import:CHERRY")
      (libsource (lib "eagle-import") (part "CHERRY"))
    )
    (comp (ref "U$59")
      (value "CHERRY")
      (footprint "eagle-import:CHERRY")
      (libsource (lib "eagle-import") (part "CHERRY"))
    )
    (comp (ref "U$60")
      (value "CHERRY")
      (footprint "eagle-import:CHERRY")
      (libsource (lib "eagle-import") (part "CHERRY"))
    )
    (comp (ref "U$61")
      (value "CHERRY")
      (footprint "eagle-import:CHERRY")
      (libsource (lib "eagle-import") (part "CHERRY"))
    )
    (comp (ref "U$63")
      (value "TP4056")
      (footprint "eagle-import:SOT23-8")
      (libsource (lib "eagle-import") (part "TP4056"))
    )
    (comp (ref "U2")
      (value "AP2112K-3.3TRG1")
      (footprint "eagle-import:SOT95P285X140-5N")
      (fields (field (name "MF") "Diodes Inc."))
      (libsource (lib "eagle-import") (part "AP2112K-3.3TRG1"))
    )
  )
  (nets
    (net (code "1") (name "/BLED") (class "Default")
      (node (ref "IC3") (pin "P0.15") (pinfunction "P0.15_P0.15") (pintype "bidirectional"))
      (node (ref "LED1") (pin "A") (pinfunction "A_A") (pintype "passive"))
    )
    (net (code "2") (name "/BVOLT") (class "Default")
      (node (ref "IC3") (pin "P0.04") (pinfunction "P0.04_P0.04") (pintype "bidirectional"))
      (node (ref "R19") (pin "2") (pinfunction "2_2") (pintype "passive"))
      (node (ref "R20") (pin "1") (pinfunction "1_1") (pintype "passive"))
    )
    (net (code "3") (name "/COL1") (class "Default")
      (node (ref "IC3") (pin "P0.10") (pinfunction "P0.10_P0.10") (pintype "bidirectional"))
      (node (ref "U$1") (pin "2") (pinfunction "1_2") (pintype "bidirectional"))
      (node (ref "U$15") (pin "2") (pinfunction "1_2") (pintype "bidirectional"))
      (node (ref "U$29") (pin "2") (pinfunction "1_2") (pintype "bidirectional"))
      (node (ref "U$42") (pin "2") (pinfunction "1_2") (pintype "bidirectional"))
      (node (ref "U$54") (pin "2") (pinfunction "1_2") (pintype "bidirectional"))
    )
    (net (code "4") (name "/COL2") (class "Default")
      (node (ref "IC3") (pin "P0.09") (pinfunction "P0.09_P0.09") (pintype "bidirectional"))
      (node (ref "U$16") (pin "2") (pinfunction "1_2") (pintype "bidirectional"))
      (node (ref "U$2") (pin "2") (pinfunction "1_2") (pintype "bidirectional"))
      (node (ref "U$30") (pin "2") (pinfunction "1_2") (pintype "bidirectional"))
      (node (ref "U$43") (pin "2") (pinfunction "1_2") (pintype "bidirectional"))
      (node (ref "U$55") (pin "2") (pinfunction "1_2") (pintype "bidirectional"))
    )
    (net (code "5") (name "/COL3") (class "Default")
      (node (ref "IC3") (pin "P1.06") (pinfunction "P1.06_P1.06") (pintype "bidirectional"))
      (node (ref "U$17") (pin "2") (pinfunction "1_2") (pintype "bidirectional"))
      (node (ref "U$3") (pin "2") (pinfunction "1_2") (pintype "bidirectional"))
      (node (ref "U$31") (pin "2") (pinfunction "1_2") (pintype "bidirectional"))
      (node (ref "U$44") (pin "2") (pinfunction "1_2") (pintype "bidirectional"))
      (node (ref "U$56") (pin "2") (pinfunction "1_2") (pintype "bidirectional"))
    )
    (net (code "6") (name "/COL4") (class "Default")
      (node (ref "IC3") (pin "P1.04") (pinfunction "P1.04_P1.04") (pintype "bidirectional"))
      (node (ref "U$18") (pin "2") (pinfunction "1_2") (pintype "bidirectional"))
      (node (ref "U$32") (pin "2") (pinfunction "1_2") (pintype "bidirectional"))
      (node (ref "U$4") (pin "2") (pinfunction "1_2") (pintype "bidirectional"))
      (node (ref "U$45") (pin "2") (pinfunction "1_2") (pintype "bidirectional"))
    )
    (net (code "7") (name "/COL5") (class "Default")
      (node (ref "IC3") (pin "P1.02") (pinfunction "P1.02_P1.02") (pintype "bidirectional"))
      (node (ref "U$19") (pin "2") (pinfunction "1_2") (pintype "bidirectional"))
      (node (ref "U$33") (pin "2") (pinfunction "1_2") (pintype "bidirectional"))
      (node (ref "U$46") (pin "2") (pinfunction "1_2") (pintype "bidirectional"))
      (node (ref "U$5") (pin "2") (pinfunction "1_2") (pintype "bidirectional"))
    )
    (net (code "8") (name "/COL6") (class "Default")
      (node (ref "IC3") (pin "P1.01") (pinfunction "P1.01_P1.01") (pintype "bidirectional"))
      (node (ref "U$20") (pin "2") (pinfunction "1_2") (pintype "bidirectional"))
      (node (ref "U$34") (pin "2") (pinfunction "1_2") (pintype "bidirectional"))
      (node (ref "U$47") (pin "2") (pinfunction "1_2") (pintype "bidirectional"))
      (node (ref "U$57") (pin "2") (pinfunction "1_2") (pintype "bidirectional"))
      (node (ref "U$6") (pin "2") (pinfunction "1_2") (pintype "bidirectional"))
    )
    (net (code "9") (name "/COL7") (class "Default")
      (node (ref "IC3") (pin "P1.03") (pinfunction "P1.03_P1.03") (pintype "bidirectional"))
      (node (ref "U$21") (pin "2") (pinfunction "1_2") (pintype "bidirectional"))
      (node (ref "U$35") (pin "2") (pinfunction "1_2") (pintype "bidirectional"))
      (node (ref "U$48") (pin "2") (pinfunction "1_2") (pintype "bidirectional"))
      (node (ref "U$7") (pin "2") (pinfunction "1_2") (pintype "bidirectional"))
    )
    (net (code "10") (name "/COL8") (class "Default")
      (node (ref "IC3") (pin "P1.00") (pinfunction "P1.00_P1.00") (pintype "bidirectional"))
      (node (ref "U$22") (pin "2") (pinfunction "1_2") (pintype "bidirectional"))
      (node (ref "U$36") (pin "2") (pinfunction "1_2") (pintype "bidirectional"))
      (node (ref "U$49") (pin "2") (pinfunction "1_2") (pintype "bidirectional"))
      (node (ref "U$8") (pin "2") (pinfunction "1_2") (pintype "bidirectional"))
    )
    (net (code "11") (name "/COL9") (class "Default")
      (node (ref "IC3") (pin "P0.22") (pinfunction "P0.22_P0.22") (pintype "bidirectional"))
      (node (ref "U$23") (pin "2") (pinfunction "1_2") (pintype "bidirectional"))
      (node (ref "U$37") (pin "2") (pinfunction "1_2") (pintype "bidirectional"))
      (node (ref "U$50") (pin "2") (pinfunction "1_2") (pintype "bidirectional"))
      (node (ref "U$58") (pin "2") (pinfunction "1_2") (pintype "bidirectional"))
      (node (ref "U$9") (pin "2") (pinfunction "1_2") (pintype "bidirectional"))
    )
    (net (code "12") (name "/COL10") (class "Default")
      (node (ref "IC3") (pin "P0.19") (pinfunction "P0.19_P0.19") (pintype "bidirectional"))
      (node (ref "U$10") (pin "2") (pinfunction "1_2") (pintype "bidirectional"))
      (node (ref "U$24") (pin "2") (pinfunction "1_2") (pintype "bidirectional"))
      (node (ref "U$38") (pin "2") (pinfunction "1_2") (pintype "bidirectional"))
      (node (ref "U$51") (pin "2") (pinfunction "1_2") (pintype "bidirectional"))
      (node (ref "U$59") (pin "2") (pinfunction "1_2") (pintype "bidirectional"))
    )
    (net (code "13") (name "/COL11") (class "Default")
      (node (ref "IC3") (pin "P0.21") (pinfunction "P0.21_P0.21") (pintype "bidirectional"))
      (node (ref "U$11") (pin "2") (pinfunction "1_2") (pintype "bidirectional"))
      (node (ref "U$25") (pin "2") (pinfunction "1_2") (pintype "bidirectional"))
      (node (ref "U$39") (pin "2") (pinfunction "1_2") (pintype "bidirectional"))
      (node (ref "U$52") (pin "2") (pinfunction "1_2") (pintype "bidirectional"))
      (node (ref "U$60") (pin "2") (pinfunction "1_2") (pintype "bidirectional"))
    )
    (net (code "14") (name "/COL12") (class "Default")
      (node (ref "IC3") (pin "P0.23") (pinfunction "P0.23_P0.23") (pintype "bidirectional"))
      (node (ref "U$12") (pin "2") (pinfunction "1_2") (pintype "bidirectional"))
      (node (ref "U$26") (pin "2") (pinfunction "1_2") (pintype "bidirectional"))
      (node (ref "U$40") (pin "2") (pinfunction "1_2") (pintype "bidirectional"))
      (node (ref "U$53") (pin "2") (pinfunction "1_2") (pintype "bidirectional"))
      (node (ref "U$61") (pin "2") (pinfunction "1_2") (pintype "bidirectional"))
    )
    (net (code "15") (name "/COL13") (class "Default")
      (node (ref "IC3") (pin "P0.12") (pinfunction "P0.12_P0.12") (pintype "bidirectional"))
      (node (ref "U$13") (pin "2") (pinfunction "1_2") (pintype "bidirectional"))
      (node (ref "U$27") (pin "2") (pinfunction "1_2") (pintype "bidirectional"))
      (node (ref "U$41") (pin "2") (pinfunction "1_2") (pintype "bidirectional"))
    )
    (net (code "16") (name "/COL14") (class "Default")
      (node (ref "IC3") (pin "P1.09") (pinfunction "P1.09_P1.09") (pintype "bidirectional"))
      (node (ref "U$14") (pin "2") (pinfunction "1_2") (pintype "bidirectional"))
      (node (ref "U$28") (pin "2") (pinfunction "1_2") (pintype "bidirectional"))
    )
    (net (code "17") (name "/D+") (class "Default")
      (node (ref "IC3") (pin "D+") (pinfunction "D+_D+") (pintype "bidirectional"))
      (node (ref "J3") (pin "A6") (pinfunction "D+_A6") (pintype "bidirectional"))
      (node (ref "J3") (pin "B6") (pinfunction "D+_B6") (pintype "bidirectional"))
    )
    (net (code "18") (name "/D-") (class "Default")
      (node (ref "IC3") (pin "D-") (pinfunction "D-_D-") (pintype "bidirectional"))
      (node (ref "J3") (pin "A7") (pinfunction "D-_A7") (pintype "bidirectional"))
      (node (ref "J3") (pin "B7") (pinfunction "D-_B7") (pintype "bidirectional"))
    )
    (net (code "19") (name "/G_BAT") (class "Default")
      (node (ref "C5") (pin "2") (pinfunction "2_2") (pintype "passive"))
      (node (ref "CN2") (pin "2") (pinfunction "1_2") (pintype "passive"))
      (node (ref "IC4") (pin "6") (pinfunction "GND_6") (pintype "bidirectional"))
      (node (ref "J4") (pin "2") (pinfunction "2_2") (pintype "passive"))
      (node (ref "Q4") (pin "3") (pinfunction "S2_3") (pintype "bidirectional"))
    )
    (net (code "20") (name "/POWER_PIN") (class "Default")
      (node (ref "IC3") (pin "P0.13") (pinfunction "P0.13_P0.13") (pintype "bidirectional"))
    )
    (net (code "21") (name "/RESET") (class "Default")
      (node (ref "IC3") (pin "P0.14") (pinfunction "P0.14_P0.14") (pintype "bidirectional"))
      (node (ref "IC3") (pin "P0.16") (pinfunction "P0.16_P0.16") (pintype "bidirectional"))
      (node (ref "IC3") (pin "P0.18") (pinfunction "P0.18_P0.18") (pintype "bidirectional"))
      (node (ref "PROG1") (pin "3") (pinfunction "3_3") (pintype "passive"))
      (node (ref "R2") (pin "2") (pinfunction "2_2") (pintype "passive"))
      (node (ref "S1") (pin "A2") (pinfunction "1_A2") (pintype "passive"))
    )
    (net (code "22") (name "/ROW1") (class "Default")
      (node (ref "D1") (pin "C") (pinfunction "C_C") (pintype "passive"))
      (node (ref "D10") (pin "C") (pinfunction "C_C") (pintype "passive"))
      (node (ref "D11") (pin "C") (pinfunction "C_C") (pintype "passive"))
      (node (ref "D12") (pin "C") (pinfunction "C_C") (pintype "passive"))
      (node (ref "D13") (pin "C") (pinfunction "C_C") (pintype "passive"))
      (node (ref "D14") (pin "C") (pinfunction "C_C") (pintype "passive"))
      (node (ref "D2") (pin "C") (pinfunction "C_C") (pintype "passive"))
      (node (ref "D3") (pin "C") (pinfunction "C_C") (pintype "passive"))
      (node (ref "D4") (pin "C") (pinfunction "C_C") (pintype "passive"))
      (node (ref "D5") (pin "C") (pinfunction "C_C") (pintype "passive"))
      (node (ref "D6") (pin "C") (pinfunction "C_C") (pintype "passive"))
      (node (ref "D7") (pin "C") (pinfunction "C_C") (pintype "passive"))
      (node (ref "D8") (pin "C") (pinfunction "C_C") (pintype "passive"))
      (node (ref "D9") (pin "C") (pinfunction "C_C") (pintype "passive"))
      (node (ref "IC3") (pin "P0.29") (pinfunction "P0.29_P0.29") (pintype "bidirectional"))
    )
    (net (code "23") (name "/ROW2") (class "Default")
      (node (ref "D15") (pin "C") (pinfunction "C_C") (pintype "passive"))
      (node (ref "D16") (pin "C") (pinfunction "C_C") (pintype "passive"))
      (node (ref "D17") (pin "C") (pinfunction "C_C") (pintype "passive"))
      (node (ref "D18") (pin "C") (pinfunction "C_C") (pintype "passive"))
      (node (ref "D19") (pin "C") (pinfunction "C_C") (pintype "passive"))
      (node (ref "D20") (pin "C") (pinfunction "C_C") (pintype "passive"))
      (node (ref "D21") (pin "C") (pinfunction "C_C") (pintype "passive"))
      (node (ref "D22") (pin "C") (pinfunction "C_C") (pintype "passive"))
      (node (ref "D23") (pin "C") (pinfunction "C_C") (pintype "passive"))
      (node (ref "D24") (pin "C") (pinfunction "C_C") (pintype "passive"))
      (node (ref "D25") (pin "C") (pinfunction "C_C") (pintype "passive"))
      (node (ref "D26") (pin "C") (pinfunction "C_C") (pintype "passive"))
      (node (ref "D27") (pin "C") (pinfunction "C_C") (pintype "passive"))
      (node (ref "D28") (pin "C") (pinfunction "C_C") (pintype "passive"))
      (node (ref "IC3") (pin "P0.30") (pinfunction "P0.30_P0.30") (pintype "bidirectional"))
    )
    (net (code "24") (name "/ROW3") (class "Default")
      (node (ref "D29") (pin "C") (pinfunction "C_C") (pintype "passive"))
      (node (ref "D30") (pin "C") (pinfunction "C_C") (pintype "passive"))
      (node (ref "D31") (pin "C") (pinfunction "C_C") (pintype "passive"))
      (node (ref "D32") (pin "C") (pinfunction "C_C") (pintype "passive"))
      (node (ref "D33") (pin "C") (pinfunction "C_C") (pintype "passive"))
      (node (ref "D34") (pin "C") (pinfunction "C_C") (pintype "passive"))
      (node (ref "D35") (pin "C") (pinfunction "C_C") (pintype "passive"))
      (node (ref "D36") (pin "C") (pinfunction "C_C") (pintype "passive"))
      (node (ref "D37") (pin "C") (pinfunction "C_C") (pintype "passive"))
      (node (ref "D38") (pin "C") (pinfunction "C_C") (pintype "passive"))
      (node (ref "D39") (pin "C") (pinfunction "C_C") (pintype "passive"))
      (node (ref "D40") (pin "C") (pinfunction "C_C") (pintype "passive"))
      (node (ref "D41") (pin "C") (pinfunction "C_C") (pintype "passive"))
      (node (ref "IC3") (pin "P0.31") (pinfunction "P0.31_P0.31") (pintype "bidirectional"))
    )
    (net (code "25") (name "/ROW4") (class "Default")
      (node (ref "D42") (pin "C") (pinfunction "C_C") (pintype "passive"))
      (node (ref "D43") (pin "C") (pinfunction "C_C") (pintype "passive"))
      (node (ref "D44") (pin "C") (pinfunction "C_C") (pintype "passive"))
      (node (ref "D45") (pin "C") (pinfunction "C_C") (pintype "passive"))
      (node (ref "D46") (pin "C") (pinfunction "C_C") (pintype "passive"))
      (node (ref "D47") (pin "C") (pinfunction "C_C") (pintype "passive"))
      (node (ref "D48") (pin "C") (pinfunction "C_C") (pintype "passive"))
      (node (ref "D49") (pin "C") (pinfunction "C_C") (pintype "passive"))
      (node (ref "D50") (pin "C") (pinfunction "C_C") (pintype "passive"))
      (node (ref "D51") (pin "C") (pinfunction "C_C") (pintype "passive"))
      (node (ref "D52") (pin "C") (pinfunction "C_C") (pintype "passive"))
      (node (ref "D53") (pin "C") (pinfunction "C_C") (pintype "passive"))
      (node (ref "IC3") (pin "P0.05") (pinfunction "P0.05_P0.05") (pintype "bidirectional"))
    )
    (net (code "26") (name "/ROW5") (class "Default")
      (node (ref "D54") (pin "C") (pinfunction "C_C") (pintype "passive"))
      (node (ref "D55") (pin "C") (pinfunction "C_C") (pintype "passive"))
      (node (ref "D56") (pin "C") (pinfunction "C_C") (pintype "passive"))
      (node (ref "D57") (pin "C") (pinfunction "C_C") (pintype "passive"))
      (node (ref "D58") (pin "C") (pinfunction "C_C") (pintype "passive"))
      (node (ref "D59") (pin "C") (pinfunction "C_C") (pintype "passive"))
      (node (ref "D60") (pin "C") (pinfunction "C_C") (pintype "passive"))
      (node (ref "D61") (pin "C") (pinfunction "C_C") (pintype "passive"))
      (node (ref "IC3") (pin "P0.07") (pinfunction "P0.07_P0.07") (pintype "bidirectional"))
    )
    (net (code "27") (name "/RXD") (class "Default")
      (node (ref "IC3") (pin "P0.08") (pinfunction "P0.08_P0.08") (pintype "bidirectional"))
    )
    (net (code "28") (name "/SCK") (class "Default")
      (node (ref "IC3") (pin "SWDCLK") (pinfunction "SWDCLK_SWDCLK") (pintype "bidirectional"))
      (node (ref "PROG1") (pin "5") (pinfunction "5_5") (pintype "passive"))
    )
    (net (code "29") (name "/SWD") (class "Default")
      (node (ref "IC3") (pin "SWDIO") (pinfunction "SWDIO_SWDIO") (pintype "bidirectional"))
      (node (ref "PROG1") (pin "4") (pinfunction "4_4") (pintype "passive"))
    )
    (net (code "30") (name "/TXD") (class "Default")
      (node (ref "IC3") (pin "P0.06") (pinfunction "P0.06_P0.06") (pintype "bidirectional"))
    )
    (net (code "31") (name "/VDD_NRF") (class "Default")
      (node (ref "IC3") (pin "VDD_NRF") (pinfunction "VDD_NRF_VDD_NRF") (pintype "bidirectional"))
      (node (ref "PROG1") (pin "1") (pinfunction "1_1") (pintype "passive"))
      (node (ref "R2") (pin "1") (pinfunction "1_1") (pintype "passive"))
      (node (ref "U2") (pin "5") (pinfunction "VOUT_5") (pintype "power_in"))
    )
    (net (code "32") (name "GND") (class "Default")
      (node (ref "C4") (pin "2") (pinfunction "2_2") (pintype "passive"))
      (node (ref "C6") (pin "2") (pinfunction "2_2") (pintype "passive"))
      (node (ref "IC3") (pin "GND") (pinfunction "GND1_GND") (pintype "bidirectional"))
      (node (ref "IC3") (pin "GND1") (pinfunction "GND2_GND1") (pintype "bidirectional"))
      (node (ref "IC3") (pin "GND2") (pinfunction "GND3_GND2") (pintype "bidirectional"))
      (node (ref "J3") (pin "GND") (pinfunction "GND_GND") (pintype "bidirectional"))
      (node (ref "J3") (pin "GND2") (pinfunction "GND_GND2") (pintype "bidirectional"))
      (node (ref "J3") (pin "SHLD1") (pinfunction "SHLD_SHLD1") (pintype "bidirectional"))
      (node (ref "J3") (pin "SHLD2") (pinfunction "SHLD_SHLD2") (pintype "bidirectional"))
      (node (ref "J3") (pin "SHLD3") (pinfunction "SHLD_SHLD3") (pintype "bidirectional"))
      (node (ref "J3") (pin "SHLD4") (pinfunction "SHLD_SHLD4") (pintype "bidirectional"))
      (node (ref "J3") (pin "SHLD5") (pinfunction "SHLD_SHLD5") (pintype "bidirectional"))
      (node (ref "J3") (pin "SHLD6") (pinfunction "SHLD_SHLD6") (pintype "bidirectional"))
      (node (ref "J3") (pin "SHLD7") (pinfunction "SHLD_SHLD7") (pintype "bidirectional"))
      (node (ref "J3") (pin "SHLD8") (pinfunction "SHLD_SHLD8") (pintype "bidirectional"))
      (node (ref "PROG1") (pin "2") (pinfunction "2_2") (pintype "passive"))
      (node (ref "Q4") (pin "1") (pinfunction "S1_1") (pintype "bidirectional"))
      (node (ref "R1") (pin "1") (pinfunction "1_1") (pintype "passive"))
      (node (ref "R11") (pin "1") (pinfunction "1_1") (pintype "passive"))
      (node (ref "R12") (pin "1") (pinfunction "1_1") (pintype "passive"))
      (node (ref "R13") (pin "1") (pinfunction "1_1") (pintype "passive"))
      (node (ref "R16") (pin "1") (pinfunction "1_1") (pintype "passive"))
      (node (ref "R17") (pin "1") (pinfunction "1_1") (pintype "passive"))
      (node (ref "R20") (pin "2") (pinfunction "2_2") (pintype "passive"))
      (node (ref "S1") (pin "B2") (pinfunction "2_B2") (pintype "passive"))
      (node (ref "U$63") (pin "1") (pinfunction "TEMP_1") (pintype "bidirectional"))
      (node (ref "U$63") (pin "3") (pinfunction "GND_3") (pintype "bidirectional"))
      (node (ref "U2") (pin "2") (pinfunction "GND_2") (pintype "power_in"))
    )
    (net (code "33") (name "Net-(D63-K)") (class "Default")
      (node (ref "C6") (pin "1") (pinfunction "1_1") (pintype "passive"))
      (node (ref "D63") (pin "1") (pinfunction "K_1") (pintype "bidirectional"))
      (node (ref "Q5") (pin "2") (pinfunction "S_2") (pintype "passive"))
      (node (ref "U2") (pin "1") (pinfunction "VIN_1") (pintype "power_in"))
      (node (ref "U2") (pin "3") (pinfunction "EN_3") (pintype "input"))
    )
    (net (code "34") (name "Net-(IC3-PadP0.17)") (class "Default")
      (node (ref "IC3") (pin "P0.17") (pinfunction "P0.17_P0.17") (pintype "bidirectional"))
      (node (ref "J1") (pin "5") (pinfunction "5_5") (pintype "passive"))
    )
    (net (code "35") (name "Net-(IC3-PadP0.20)") (class "Default")
      (node (ref "IC3") (pin "P0.20") (pinfunction "P0.20_P0.20") (pintype "bidirectional"))
      (node (ref "J1") (pin "4") (pinfunction "4_4") (pintype "passive"))
    )
    (net (code "36") (name "Net-(IC3-PadP0.24)") (class "Default")
      (node (ref "IC3") (pin "P0.24") (pinfunction "P0.24_P0.24") (pintype "bidirectional"))
      (node (ref "J1") (pin "3") (pinfunction "3_3") (pintype "passive"))
    )
    (net (code "37") (name "Net-(IC3-PadP1.05)") (class "Default")
      (node (ref "IC3") (pin "P1.05") (pinfunction "P1.05_P1.05") (pintype "bidirectional"))
      (node (ref "J1") (pin "2") (pinfunction "2_2") (pintype "passive"))
    )
    (net (code "38") (name "Net-(IC3-PadP1.07)") (class "Default")
      (node (ref "IC3") (pin "P1.07") (pinfunction "P1.07_P1.07") (pintype "bidirectional"))
      (node (ref "J1") (pin "1") (pinfunction "1_1") (pintype "passive"))
    )
    (net (code "39") (name "Net-(IC4-CS)") (class "Default")
      (node (ref "IC4") (pin "2") (pinfunction "CS_2") (pintype "bidirectional"))
      (node (ref "R16") (pin "2") (pinfunction "2_2") (pintype "passive"))
    )
    (net (code "40") (name "Net-(IC4-OC)") (class "Default")
      (node (ref "IC4") (pin "3") (pinfunction "OC_3") (pintype "bidirectional"))
      (node (ref "Q4") (pin "4") (pinfunction "G2_4") (pintype "bidirectional"))
    )
    (net (code "41") (name "Net-(IC4-OD)") (class "Default")
      (node (ref "IC4") (pin "1") (pinfunction "OD_1") (pintype "bidirectional"))
      (node (ref "Q4") (pin "6") (pinfunction "G1_6") (pintype "bidirectional"))
    )
    (net (code "42") (name "Net-(IC4-VCC)") (class "Default")
      (node (ref "C5") (pin "1") (pinfunction "1_1") (pintype "passive"))
      (node (ref "IC4") (pin "5") (pinfunction "VCC_5") (pintype "bidirectional"))
      (node (ref "R15") (pin "1") (pinfunction "1_1") (pintype "passive"))
    )
    (net (code "43") (name "Net-(J3-CC1)") (class "Default")
      (node (ref "J3") (pin "A5") (pinfunction "CC1_A5") (pintype "bidirectional"))
      (node (ref "R12") (pin "2") (pinfunction "2_2") (pintype "passive"))
    )
    (net (code "44") (name "Net-(J3-CC2)") (class "Default")
      (node (ref "J3") (pin "B5") (pinfunction "CC2_B5") (pintype "bidirectional"))
      (node (ref "R11") (pin "2") (pinfunction "2_2") (pintype "passive"))
    )
    (net (code "45") (name "Net-(LED1-PadC)") (class "Default")
      (node (ref "LED1") (pin "C") (pinfunction "C_C") (pintype "passive"))
      (node (ref "R1") (pin "2") (pinfunction "2_2") (pintype "passive"))
    )
    (net (code "46") (name "Net-(LED2-PadC)") (class "Default")
      (node (ref "LED2") (pin "C") (pinfunction "C_C") (pintype "passive"))
      (node (ref "R14") (pin "1") (pinfunction "1_1") (pintype "passive"))
    )
    (net (code "47") (name "Net-(U$1-2)") (class "Default")
      (node (ref "D1") (pin "A") (pinfunction "A_A") (pintype "passive"))
      (node (ref "U$1") (pin "1") (pinfunction "2_1") (pintype "bidirectional"))
    )
    (net (code "48") (name "Net-(U$2-2)") (class "Default")
      (node (ref "D2") (pin "A") (pinfunction "A_A") (pintype "passive"))
      (node (ref "U$2") (pin "1") (pinfunction "2_1") (pintype "bidirectional"))
    )
    (net (code "49") (name "Net-(U$3-2)") (class "Default")
      (node (ref "D3") (pin "A") (pinfunction "A_A") (pintype "passive"))
      (node (ref "U$3") (pin "1") (pinfunction "2_1") (pintype "bidirectional"))
    )
    (net (code "50") (name "Net-(U$4-2)") (class "Default")
      (node (ref "D4") (pin "A") (pinfunction "A_A") (pintype "passive"))
      (node (ref "U$4") (pin "1") (pinfunction "2_1") (pintype "bidirectional"))
    )
    (net (code "51") (name "Net-(U$5-2)") (class "Default")
      (node (ref "D5") (pin "A") (pinfunction "A_A") (pintype "passive"))
      (node (ref "U$5") (pin "1") (pinfunction "2_1") (pintype "bidirectional"))
    )
    (net (code "52") (name "Net-(U$6-2)") (class "Default")
      (node (ref "D6") (pin "A") (pinfunction "A_A") (pintype "passive"))
      (node (ref "U$6") (pin "1") (pinfunction "2_1") (pintype "bidirectional"))
    )
    (net (code "53") (name "Net-(U$7-2)") (class "Default")
      (node (ref "D7") (pin "A") (pinfunction "A_A") (pintype "passive"))
      (node (ref "U$7") (pin "1") (pinfunction "2_1") (pintype "bidirectional"))
    )
    (net (code "54") (name "Net-(U$8-2)") (class "Default")
      (node (ref "D8") (pin "A") (pinfunction "A_A") (pintype "passive"))
      (node (ref "U$8") (pin "1") (pinfunction "2_1") (pintype "bidirectional"))
    )
    (net (code "55") (name "Net-(U$9-2)") (class "Default")
      (node (ref "D9") (pin "A") (pinfunction "A_A") (pintype "passive"))
      (node (ref "U$9") (pin "1") (pinfunction "2_1") (pintype "bidirectional"))
    )
    (net (code "56") (name "Net-(U$10-2)") (class "Default")
      (node (ref "D10") (pin "A") (pinfunction "A_A") (pintype "passive"))
      (node (ref "U$10") (pin "1") (pinfunction "2_1") (pintype "bidirectional"))
    )
    (net (code "57") (name "Net-(U$11-2)") (class "Default")
      (node (ref "D11") (pin "A") (pinfunction "A_A") (pintype "passive"))
      (node (ref "U$11") (pin "1") (pinfunction "2_1") (pintype "bidirectional"))
    )
    (net (code "58") (name "Net-(U$12-2)") (class "Default")
      (node (ref "D12") (pin "A") (pinfunction "A_A") (pintype "passive"))
      (node (ref "U$12") (pin "1") (pinfunction "2_1") (pintype "bidirectional"))
    )
    (net (code "59") (name "Net-(U$13-2)") (class "Default")
      (node (ref "D13") (pin "A") (pinfunction "A_A") (pintype "passive"))
      (node (ref "U$13") (pin "1") (pinfunction "2_1") (pintype "bidirectional"))
    )
    (net (code "60") (name "Net-(U$14-2)") (class "Default")
      (node (ref "D14") (pin "A") (pinfunction "A_A") (pintype "passive"))
      (node (ref "U$14") (pin "1") (pinfunction "2_1") (pintype "bidirectional"))
    )
    (net (code "61") (name "Net-(U$15-2)") (class "Default")
      (node (ref "D15") (pin "A") (pinfunction "A_A") (pintype "passive"))
      (node (ref "U$15") (pin "1") (pinfunction "2_1") (pintype "bidirectional"))
    )
    (net (code "62") (name "Net-(U$16-2)") (class "Default")
      (node (ref "D16") (pin "A") (pinfunction "A_A") (pintype "passive"))
      (node (ref "U$16") (pin "1") (pinfunction "2_1") (pintype "bidirectional"))
    )
    (net (code "63") (name "Net-(U$17-2)") (class "Default")
      (node (ref "D17") (pin "A") (pinfunction "A_A") (pintype "passive"))
      (node (ref "U$17") (pin "1") (pinfunction "2_1") (pintype "bidirectional"))
    )
    (net (code "64") (name "Net-(U$18-2)") (class "Default")
      (node (ref "D18") (pin "A") (pinfunction "A_A") (pintype "passive"))
      (node (ref "U$18") (pin "1") (pinfunction "2_1") (pintype "bidirectional"))
    )
    (net (code "65") (name "Net-(U$19-2)") (class "Default")
      (node (ref "D19") (pin "A") (pinfunction "A_A") (pintype "passive"))
      (node (ref "U$19") (pin "1") (pinfunction "2_1") (pintype "bidirectional"))
    )
    (net (code "66") (name "Net-(U$20-2)") (class "Default")
      (node (ref "D20") (pin "A") (pinfunction "A_A") (pintype "passive"))
      (node (ref "U$20") (pin "1") (pinfunction "2_1") (pintype "bidirectional"))
    )
    (net (code "67") (name "Net-(U$21-2)") (class "Default")
      (node (ref "D21") (pin "A") (pinfunction "A_A") (pintype "passive"))
      (node (ref "U$21") (pin "1") (pinfunction "2_1") (pintype "bidirectional"))
    )
    (net (code "68") (name "Net-(U$22-2)") (class "Default")
      (node (ref "D22") (pin "A") (pinfunction "A_A") (pintype "passive"))
      (node (ref "U$22") (pin "1") (pinfunction "2_1") (pintype "bidirectional"))
    )
    (net (code "69") (name "Net-(U$23-2)") (class "Default")
      (node (ref "D23") (pin "A") (pinfunction "A_A") (pintype "passive"))
      (node (ref "U$23") (pin "1") (pinfunction "2_1") (pintype "bidirectional"))
    )
    (net (code "70") (name "Net-(U$24-2)") (class "Default")
      (node (ref "D24") (pin "A") (pinfunction "A_A") (pintype "passive"))
      (node (ref "U$24") (pin "1") (pinfunction "2_1") (pintype "bidirectional"))
    )
    (net (code "71") (name "Net-(U$25-2)") (class "Default")
      (node (ref "D25") (pin "A") (pinfunction "A_A") (pintype "passive"))
      (node (ref "U$25") (pin "1") (pinfunction "2_1") (pintype "bidirectional"))
    )
    (net (code "72") (name "Net-(U$26-2)") (class "Default")
      (node (ref "D26") (pin "A") (pinfunction "A_A") (pintype "passive"))
      (node (ref "U$26") (pin "1") (pinfunction "2_1") (pintype "bidirectional"))
    )
    (net (code "73") (name "Net-(U$27-2)") (class "Default")
      (node (ref "D27") (pin "A") (pinfunction "A_A") (pintype "passive"))
      (node (ref "U$27") (pin "1") (pinfunction "2_1") (pintype "bidirectional"))
    )
    (net (code "74") (name "Net-(U$28-2)") (class "Default")
      (node (ref "D28") (pin "A") (pinfunction "A_A") (pintype "passive"))
      (node (ref "U$28") (pin "1") (pinfunction "2_1") (pintype "bidirectional"))
    )
    (net (code "75") (name "Net-(U$29-2)") (class "Default")
      (node (ref "D29") (pin "A") (pinfunction "A_A") (pintype "passive"))
      (node (ref "U$29") (pin "1") (pinfunction "2_1") (pintype "bidirectional"))
    )
    (net (code "76") (name "Net-(U$30-2)") (class "Default")
      (node (ref "D30") (pin "A") (pinfunction "A_A") (pintype "passive"))
      (node (ref "U$30") (pin "1") (pinfunction "2_1") (pintype "bidirectional"))
    )
    (net (code "77") (name "Net-(U$31-2)") (class "Default")
      (node (ref "D31") (pin "A") (pinfunction "A_A") (pintype "passive"))
      (node (ref "U$31") (pin "1") (pinfunction "2_1") (pintype "bidirectional"))
    )
    (net (code "78") (name "Net-(U$32-2)") (class "Default")
      (node (ref "D32") (pin "A") (pinfunction "A_A") (pintype "passive"))
      (node (ref "U$32") (pin "1") (pinfunction "2_1") (pintype "bidirectional"))
    )
    (net (code "79") (name "Net-(U$33-2)") (class "Default")
      (node (ref "D33") (pin "A") (pinfunction "A_A") (pintype "passive"))
      (node (ref "U$33") (pin "1") (pinfunction "2_1") (pintype "bidirectional"))
    )
    (net (code "80") (name "Net-(U$34-2)") (class "Default")
      (node (ref "D34") (pin "A") (pinfunction "A_A") (pintype "passive"))
      (node (ref "U$34") (pin "1") (pinfunction "2_1") (pintype "bidirectional"))
    )
    (net (code "81") (name "Net-(U$35-2)") (class "Default")
      (node (ref "D35") (pin "A") (pinfunction "A_A") (pintype "passive"))
      (node (ref "U$35") (pin "1") (pinfunction "2_1") (pintype "bidirectional"))
    )
    (net (code "82") (name "Net-(U$36-2)") (class "Default")
      (node (ref "D36") (pin "A") (pinfunction "A_A") (pintype "passive"))
      (node (ref "U$36") (pin "1") (pinfunction "2_1") (pintype "bidirectional"))
    )
    (net (code "83") (name "Net-(U$37-2)") (class "Default")
      (node (ref "D37") (pin "A") (pinfunction "A_A") (pintype "passive"))
      (node (ref "U$37") (pin "1") (pinfunction "2_1") (pintype "bidirectional"))
    )
    (net (code "84") (name "Net-(U$38-2)") (class "Default")
      (node (ref "D38") (pin "A") (pinfunction "A_A") (pintype "passive"))
      (node (ref "U$38") (pin "1") (pinfunction "2_1") (pintype "bidirectional"))
    )
    (net (code "85") (name "Net-(U$39-2)") (class "Default")
      (node (ref "D39") (pin "A") (pinfunction "A_A") (pintype "passive"))
      (node (ref "U$39") (pin "1") (pinfunction "2_1") (pintype "bidirectional"))
    )
    (net (code "86") (name "Net-(U$40-2)") (class "Default")
      (node (ref "D40") (pin "A") (pinfunction "A_A") (pintype "passive"))
      (node (ref "U$40") (pin "1") (pinfunction "2_1") (pintype "bidirectional"))
    )
    (net (code "87") (name "Net-(U$41-2)") (class "Default")
      (node (ref "D41") (pin "A") (pinfunction "A_A") (pintype "passive"))
      (node (ref "U$41") (pin "1") (pinfunction "2_1") (pintype "bidirectional"))
    )
    (net (code "88") (name "Net-(U$42-2)") (class "Default")
      (node (ref "D42") (pin "A") (pinfunction "A_A") (pintype "passive"))
      (node (ref "U$42") (pin "1") (pinfunction "2_1") (pintype "bidirectional"))
    )
    (net (code "89") (name "Net-(U$43-2)") (class "Default")
      (node (ref "D43") (pin "A") (pinfunction "A_A") (pintype "passive"))
      (node (ref "U$43") (pin "1") (pinfunction "2_1") (pintype "bidirectional"))
    )
    (net (code "90") (name "Net-(U$44-2)") (class "Default")
      (node (ref "D44") (pin "A") (pinfunction "A_A") (pintype "passive"))
      (node (ref "U$44") (pin "1") (pinfunction "2_1") (pintype "bidirectional"))
    )
    (net (code "91") (name "Net-(U$45-2)") (class "Default")
      (node (ref "D45") (pin "A") (pinfunction "A_A") (pintype "passive"))
      (node (ref "U$45") (pin "1") (pinfunction "2_1") (pintype "bidirectional"))
    )
    (net (code "92") (name "Net-(U$46-2)") (class "Default")
      (node (ref "D46") (pin "A") (pinfunction "A_A") (pintype "passive"))
      (node (ref "U$46") (pin "1") (pinfunction "2_1") (pintype "bidirectional"))
    )
    (net (code "93") (name "Net-(U$47-2)") (class "Default")
      (node (ref "D47") (pin "A") (pinfunction "A_A") (pintype "passive"))
      (node (ref "U$47") (pin "1") (pinfunction "2_1") (pintype "bidirectional"))
    )
    (net (code "94") (name "Net-(U$48-2)") (class "Default")
      (node (ref "D48") (pin "A") (pinfunction "A_A") (pintype "passive"))
      (node (ref "U$48") (pin "1") (pinfunction "2_1") (pintype "bidirectional"))
    )
    (net (code "95") (name "Net-(U$49-2)") (class "Default")
      (node (ref "D49") (pin "A") (pinfunction "A_A") (pintype "passive"))
      (node (ref "U$49") (pin "1") (pinfunction "2_1") (pintype "bidirectional"))
    )
    (net (code "96") (name "Net-(U$50-2)") (class "Default")
      (node (ref "D50") (pin "A") (pinfunction "A_A") (pintype "passive"))
      (node (ref "U$50") (pin "1") (pinfunction "2_1") (pintype "bidirectional"))
    )
    (net (code "97") (name "Net-(U$51-2)") (class "Default")
      (node (ref "D51") (pin "A") (pinfunction "A_A") (pintype "passive"))
      (node (ref "U$51") (pin "1") (pinfunction "2_1") (pintype "bidirectional"))
    )
    (net (code "98") (name "Net-(U$52-2)") (class "Default")
      (node (ref "D52") (pin "A") (pinfunction "A_A") (pintype "passive"))
      (node (ref "U$52") (pin "1") (pinfunction "2_1") (pintype "bidirectional"))
    )
    (net (code "99") (name "Net-(U$53-2)") (class "Default")
      (node (ref "D53") (pin "A") (pinfunction "A_A") (pintype "passive"))
      (node (ref "U$53") (pin "1") (pinfunction "2_1") (pintype "bidirectional"))
    )
    (net (code "100") (name "Net-(U$54-2)") (class "Default")
      (node (ref "D54") (pin "A") (pinfunction "A_A") (pintype "passive"))
      (node (ref "U$54") (pin "1") (pinfunction "2_1") (pintype "bidirectional"))
    )
    (net (code "101") (name "Net-(U$55-2)") (class "Default")
      (node (ref "D55") (pin "A") (pinfunction "A_A") (pintype "passive"))
      (node (ref "U$55") (pin "1") (pinfunction "2_1") (pintype "bidirectional"))
    )
    (net (code "102") (name "Net-(U$56-2)") (class "Default")
      (node (ref "D56") (pin "A") (pinfunction "A_A") (pintype "passive"))
      (node (ref "U$56") (pin "1") (pinfunction "2_1") (pintype "bidirectional"))
    )
    (net (code "103") (name "Net-(U$57-2)") (class "Default")
      (node (ref "D57") (pin "A") (pinfunction "A_A") (pintype "passive"))
      (node (ref "U$57") (pin "1") (pinfunction "2_1") (pintype "bidirectional"))
    )
    (net (code "104") (name "Net-(U$58-2)") (class "Default")
      (node (ref "D58") (pin "A") (pinfunction "A_A") (pintype "passive"))
      (node (ref "U$58") (pin "1") (pinfunction "2_1") (pintype "bidirectional"))
    )
    (net (code "105") (name "Net-(U$59-2)") (class "Default")
      (node (ref "D59") (pin "A") (pinfunction "A_A") (pintype "passive"))
      (node (ref "U$59") (pin "1") (pinfunction "2_1") (pintype "bidirectional"))
    )
    (net (code "106") (name "Net-(U$60-2)") (class "Default")
      (node (ref "D60") (pin "A") (pinfunction "A_A") (pintype "passive"))
      (node (ref "U$60") (pin "1") (pinfunction "2_1") (pintype "bidirectional"))
    )
    (net (code "107") (name "Net-(U$61-2)") (class "Default")
      (node (ref "D61") (pin "A") (pinfunction "A_A") (pintype "passive"))
      (node (ref "U$61") (pin "1") (pinfunction "2_1") (pintype "bidirectional"))
    )
    (net (code "108") (name "Net-(U$63-PROG)") (class "Default")
      (node (ref "R13") (pin "2") (pinfunction "2_2") (pintype "passive"))
      (node (ref "U$63") (pin "2") (pinfunction "PROG_2") (pintype "bidirectional"))
    )
    (net (code "109") (name "Net-(U$63-~{CHRG})") (class "Default")
      (node (ref "R14") (pin "2") (pinfunction "2_2") (pintype "passive"))
      (node (ref "U$63") (pin "7") (pinfunction "~{CHRG}_7") (pintype "bidirectional"))
    )
    (net (code "110") (name "V_BATT") (class "Default")
      (node (ref "CN2") (pin "1") (pinfunction "2_1") (pintype "passive"))
      (node (ref "J4") (pin "1") (pinfunction "1_1") (pintype "passive"))
      (node (ref "Q5") (pin "3") (pinfunction "D_3") (pintype "passive"))
      (node (ref "R15") (pin "2") (pinfunction "2_2") (pintype "passive"))
      (node (ref "R19") (pin "1") (pinfunction "1_1") (pintype "passive"))
      (node (ref "U$63") (pin "5") (pinfunction "BAT_5") (pintype "bidirectional"))
    )
    (net (code "111") (name "V_USB") (class "Default")
      (node (ref "C4") (pin "1") (pinfunction "1_1") (pintype "passive"))
      (node (ref "D63") (pin "2") (pinfunction "A_2") (pintype "bidirectional"))
      (node (ref "IC3") (pin "VBUS") (pinfunction "VBUS_VBUS") (pintype "bidirectional"))
      (node (ref "J3") (pin "VBUS1") (pinfunction "VBUS_VBUS1") (pintype "bidirectional"))
      (node (ref "J3") (pin "VBUS2") (pinfunction "VBUS_VBUS2") (pintype "bidirectional"))
      (node (ref "LED2") (pin "A") (pinfunction "A_A") (pintype "passive"))
      (node (ref "Q5") (pin "1") (pinfunction "G_1") (pintype "passive"))
      (node (ref "R17") (pin "2") (pinfunction "2_2") (pintype "passive"))
      (node (ref "U$63") (pin "4") (pinfunction "VCC_4") (pintype "bidirectional"))
      (node (ref "U$63") (pin "8") (pinfunction "CE_8") (pintype "bidirectional"))
    )
    (net (code "112") (name "unconnected-(IC3-PadP0.02)") (class "Default")
      (node (ref "IC3") (pin "P0.02") (pinfunction "P0.02_P0.02") (pintype "bidirectional"))
    )
    (net (code "113") (name "unconnected-(IC3-PadP0.03)") (class "Default")
      (node (ref "IC3") (pin "P0.03") (pinfunction "P0.03_P0.03") (pintype "bidirectional"))
    )
    (net (code "114") (name "unconnected-(IC3-PadP0.11)") (class "Default")
      (node (ref "IC3") (pin "P0.11") (pinfunction "P0.11_P0.11") (pintype "bidirectional"))
    )
    (net (code "115") (name "unconnected-(IC3-PadP0.25)") (class "Default")
      (node (ref "IC3") (pin "P0.25") (pinfunction "P0.25_P0.25") (pintype "bidirectional"))
    )
    (net (code "116") (name "unconnected-(IC3-PadP0.26)") (class "Default")
      (node (ref "IC3") (pin "P0.26") (pinfunction "P0.26_P0.26") (pintype "bidirectional"))
    )
    (net (code "117") (name "unconnected-(IC3-PadP0.27)") (class "Default")
      (node (ref "IC3") (pin "P0.27") (pinfunction "P0.27_P0.27") (pintype "bidirectional"))
    )
    (net (code "118") (name "unconnected-(IC3-PadP0.28)") (class "Default")
      (node (ref "IC3") (pin "P0.28") (pinfunction "P0.28_P0.28") (pintype "bidirectional"))
    )
    (net (code "119") (name "unconnected-(IC3-PadP1.08)") (class "Default")
      (node (ref "IC3") (pin "P1.08") (pinfunction "P1.08_P1.08") (pintype "bidirectional"))
    )
    (net (code "120") (name "unconnected-(IC3-PadP1.10)") (class "Default")
      (node (ref "IC3") (pin "P1.10") (pinfunction "P1.10_P1.10") (pintype "bidirectional"))
    )
    (net (code "121") (name "unconnected-(IC3-PadP1.11)") (class "Default")
      (node (ref "IC3") (pin "P1.11") (pinfunction "P1.11_P1.11") (pintype "bidirectional"))
    )
    (net (code "122") (name "unconnected-(IC3-PadP1.12)") (class "Default")
      (node (ref "IC3") (pin "P1.12") (pinfunction "P1.12_P1.12") (pintype "bidirectional"))
    )
    (net (code "123") (name "unconnected-(IC3-PadP1.13)") (class "Default")
      (node (ref "IC3") (pin "P1.13") (pinfunction "P1.13_P1.13") (pintype "bidirectional"))
    )
    (net (code "124") (name "unconnected-(IC3-PadP1.14)") (class "Default")
      (node (ref "IC3") (pin "P1.14") (pinfunction "P1.14_P1.14") (pintype "bidirectional"))
    )
    (net (code "125") (name "unconnected-(IC3-PadP1.15)") (class "Default")
      (node (ref "IC3") (pin "P1.15") (pinfunction "P1.15_P1.15") (pintype "bidirectional"))
    )
    (net (code "126") (name "unconnected-(IC4-TD-Pad4)") (class "Default")
      (node (ref "IC4") (pin "4") (pinfunction "TD_4") (pintype "bidirectional"))
    )
    (net (code "127") (name "unconnected-(Q4-D12_1-Pad2)") (class "Default")
      (node (ref "Q4") (pin "2") (pinfunction "D12_1_2") (pintype "bidirectional"))
    )
    (net (code "128") (name "unconnected-(Q4-D12_2-Pad5)") (class "Default")
      (node (ref "Q4") (pin "5") (pinfunction "D12_2_5") (pintype "bidirectional"))
    )
    (net (code "129") (name "unconnected-(U$63-~{STDBY}-Pad6)") (class "Default")
      (node (ref "U$63") (pin "6") (pinfunction "~{STDBY}_6") (pintype "bidirectional"))
    )
  )
)
